# operacake.net
KiCad netlist of a schematic drawn in Altium Designer
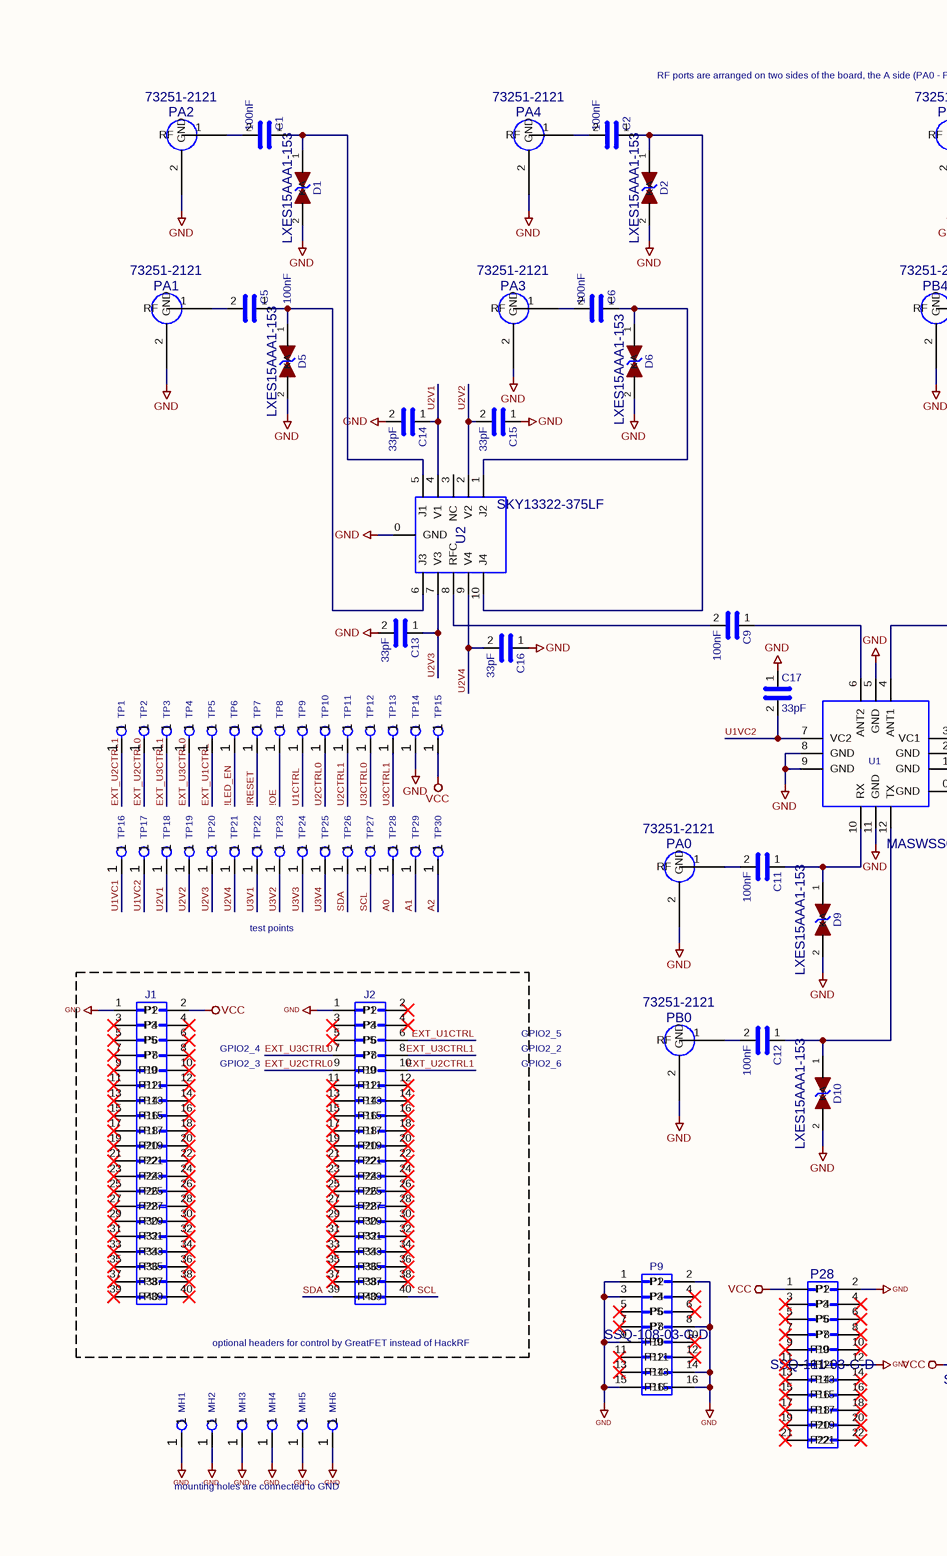
[diagram p0: operacake.SchDoc, left]
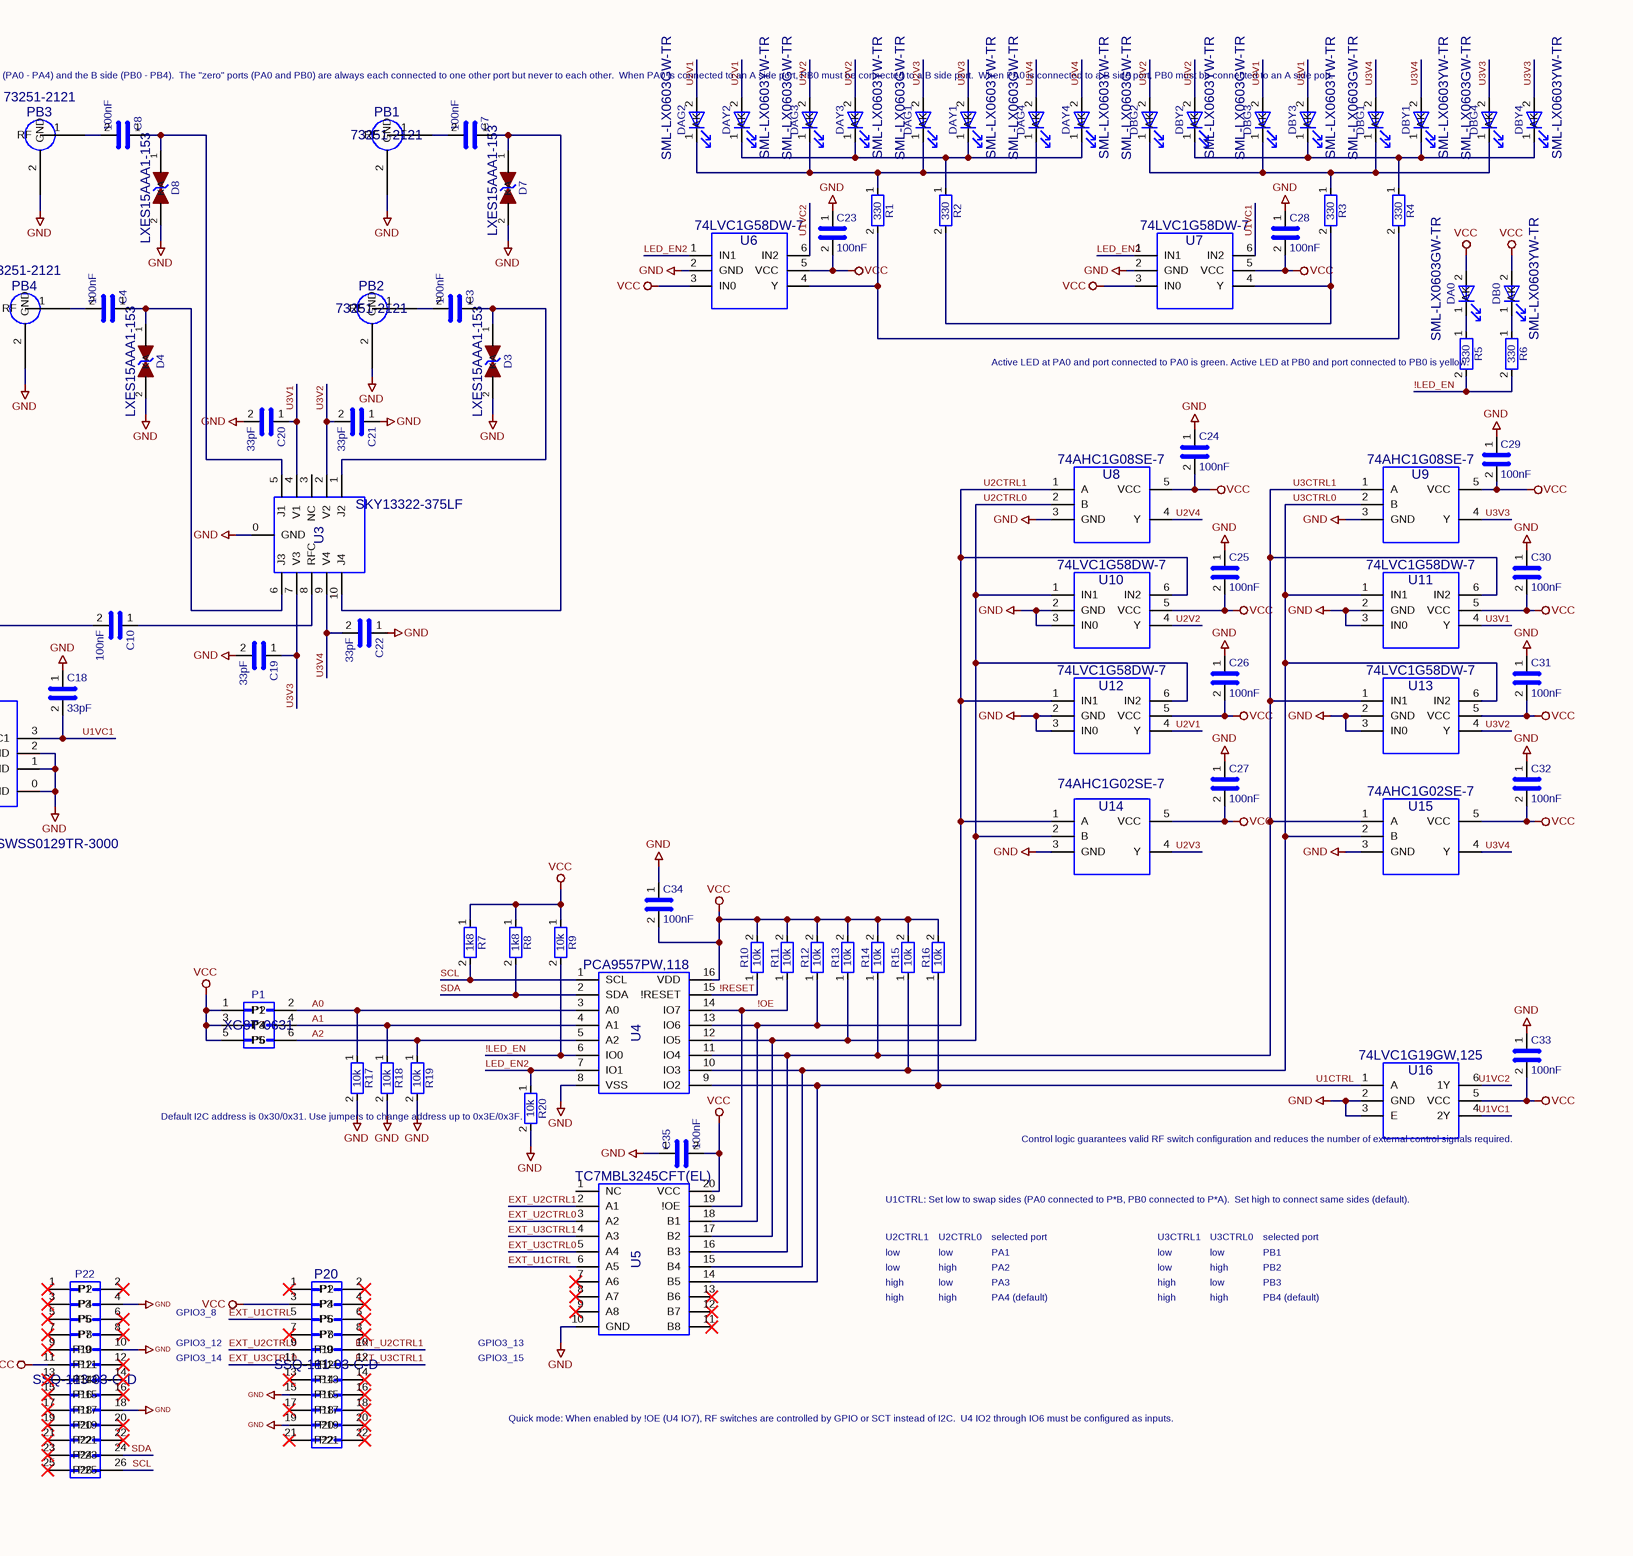
[diagram p1: operacake.SchDoc, right]

(export (version "E")
  (design (tool "Eeschema 10.0.6"))
  (components
    (comp (ref "C1")
      (value "100nF")
      (footprint "0402")
      (fields (field (name "MANUFACTURER") "Murata") (field (name "PART NUMBER") "GRM155R61A104KA01D"))
      (libsource (lib "operacake-rescue") (part "C"))
    )
    (comp (ref "C2")
      (value "100nF")
      (footprint "0402")
      (fields (field (name "MANUFACTURER") "Murata") (field (name "PART NUMBER") "GRM155R61A104KA01D"))
      (libsource (lib "operacake-rescue") (part "C"))
    )
    (comp (ref "C3")
      (value "100nF")
      (footprint "0402")
      (fields (field (name "MANUFACTURER") "Murata") (field (name "PART NUMBER") "GRM155R61A104KA01D"))
      (libsource (lib "operacake-rescue") (part "C"))
    )
    (comp (ref "C4")
      (value "100nF")
      (footprint "0402")
      (fields (field (name "MANUFACTURER") "Murata") (field (name "PART NUMBER") "GRM155R61A104KA01D"))
      (libsource (lib "operacake-rescue") (part "C"))
    )
    (comp (ref "C5")
      (value "100nF")
      (footprint "0402")
      (fields (field (name "MANUFACTURER") "Murata") (field (name "PART NUMBER") "GRM155R61A104KA01D"))
      (libsource (lib "operacake-rescue") (part "C"))
    )
    (comp (ref "C6")
      (value "100nF")
      (footprint "0402")
      (fields (field (name "MANUFACTURER") "Murata") (field (name "PART NUMBER") "GRM155R61A104KA01D"))
      (libsource (lib "operacake-rescue") (part "C"))
    )
    (comp (ref "C7")
      (value "100nF")
      (footprint "0402")
      (fields (field (name "MANUFACTURER") "Murata") (field (name "PART NUMBER") "GRM155R61A104KA01D"))
      (libsource (lib "operacake-rescue") (part "C"))
    )
    (comp (ref "C8")
      (value "100nF")
      (footprint "0402")
      (fields (field (name "MANUFACTURER") "Murata") (field (name "PART NUMBER") "GRM155R61A104KA01D"))
      (libsource (lib "operacake-rescue") (part "C"))
    )
    (comp (ref "C9")
      (value "100nF")
      (footprint "0402")
      (fields (field (name "MANUFACTURER") "Murata") (field (name "PART NUMBER") "GRM155R61A104KA01D"))
      (libsource (lib "operacake-rescue") (part "C"))
    )
    (comp (ref "C10")
      (value "100nF")
      (footprint "0402")
      (fields (field (name "MANUFACTURER") "Murata") (field (name "PART NUMBER") "GRM155R61A104KA01D"))
      (libsource (lib "operacake-rescue") (part "C"))
    )
    (comp (ref "C11")
      (value "100nF")
      (footprint "0402")
      (fields (field (name "MANUFACTURER") "Murata") (field (name "PART NUMBER") "GRM155R61A104KA01D"))
      (libsource (lib "operacake-rescue") (part "C"))
    )
    (comp (ref "C12")
      (value "100nF")
      (footprint "0402")
      (fields (field (name "MANUFACTURER") "Murata") (field (name "PART NUMBER") "GRM155R61A104KA01D"))
      (libsource (lib "operacake-rescue") (part "C"))
    )
    (comp (ref "C13")
      (value "33pF")
      (footprint "0402")
      (fields (field (name "MANUFACTURER") "Murata") (field (name "PART NUMBER") "GRM1555C1H330JA01D"))
      (libsource (lib "operacake-rescue") (part "C"))
    )
    (comp (ref "C14")
      (value "33pF")
      (footprint "0402")
      (fields (field (name "MANUFACTURER") "Murata") (field (name "PART NUMBER") "GRM1555C1H330JA01D"))
      (libsource (lib "operacake-rescue") (part "C"))
    )
    (comp (ref "C15")
      (value "33pF")
      (footprint "0402")
      (fields (field (name "MANUFACTURER") "Murata") (field (name "PART NUMBER") "GRM1555C1H330JA01D"))
      (libsource (lib "operacake-rescue") (part "C"))
    )
    (comp (ref "C16")
      (value "33pF")
      (footprint "0402")
      (fields (field (name "MANUFACTURER") "Murata") (field (name "PART NUMBER") "GRM1555C1H330JA01D"))
      (libsource (lib "operacake-rescue") (part "C"))
    )
    (comp (ref "C17")
      (value "33pF")
      (footprint "0402")
      (fields (field (name "MANUFACTURER") "Murata") (field (name "PART NUMBER") "GRM1555C1H330JA01D"))
      (libsource (lib "operacake-rescue") (part "C"))
    )
    (comp (ref "C18")
      (value "33pF")
      (footprint "0402")
      (fields (field (name "MANUFACTURER") "Murata") (field (name "PART NUMBER") "GRM1555C1H330JA01D"))
      (libsource (lib "operacake-rescue") (part "C"))
    )
    (comp (ref "C19")
      (value "33pF")
      (footprint "0402")
      (fields (field (name "MANUFACTURER") "Murata") (field (name "PART NUMBER") "GRM1555C1H330JA01D"))
      (libsource (lib "operacake-rescue") (part "C"))
    )
    (comp (ref "C20")
      (value "33pF")
      (footprint "0402")
      (fields (field (name "MANUFACTURER") "Murata") (field (name "PART NUMBER") "GRM1555C1H330JA01D"))
      (libsource (lib "operacake-rescue") (part "C"))
    )
    (comp (ref "C21")
      (value "33pF")
      (footprint "0402")
      (fields (field (name "MANUFACTURER") "Murata") (field (name "PART NUMBER") "GRM1555C1H330JA01D"))
      (libsource (lib "operacake-rescue") (part "C"))
    )
    (comp (ref "C22")
      (value "33pF")
      (footprint "0402")
      (fields (field (name "MANUFACTURER") "Murata") (field (name "PART NUMBER") "GRM1555C1H330JA01D"))
      (libsource (lib "operacake-rescue") (part "C"))
    )
    (comp (ref "C23")
      (value "100nF")
      (footprint "0402")
      (fields (field (name "MANUFACTURER") "Murata") (field (name "PART NUMBER") "GRM155R61A104KA01D"))
      (libsource (lib "operacake-rescue") (part "C"))
    )
    (comp (ref "C24")
      (value "100nF")
      (footprint "0402")
      (fields (field (name "MANUFACTURER") "Murata") (field (name "PART NUMBER") "GRM155R61A104KA01D"))
      (libsource (lib "operacake-rescue") (part "C"))
    )
    (comp (ref "C25")
      (value "100nF")
      (footprint "0402")
      (fields (field (name "MANUFACTURER") "Murata") (field (name "PART NUMBER") "GRM155R61A104KA01D"))
      (libsource (lib "operacake-rescue") (part "C"))
    )
    (comp (ref "C26")
      (value "100nF")
      (footprint "0402")
      (fields (field (name "MANUFACTURER") "Murata") (field (name "PART NUMBER") "GRM155R61A104KA01D"))
      (libsource (lib "operacake-rescue") (part "C"))
    )
    (comp (ref "C27")
      (value "100nF")
      (footprint "0402")
      (fields (field (name "MANUFACTURER") "Murata") (field (name "PART NUMBER") "GRM155R61A104KA01D"))
      (libsource (lib "operacake-rescue") (part "C"))
    )
    (comp (ref "C28")
      (value "100nF")
      (footprint "0402")
      (fields (field (name "MANUFACTURER") "Murata") (field (name "PART NUMBER") "GRM155R61A104KA01D"))
      (libsource (lib "operacake-rescue") (part "C"))
    )
    (comp (ref "C29")
      (value "100nF")
      (footprint "0402")
      (fields (field (name "MANUFACTURER") "Murata") (field (name "PART NUMBER") "GRM155R61A104KA01D"))
      (libsource (lib "operacake-rescue") (part "C"))
    )
    (comp (ref "C30")
      (value "100nF")
      (footprint "0402")
      (fields (field (name "MANUFACTURER") "Murata") (field (name "PART NUMBER") "GRM155R61A104KA01D"))
      (libsource (lib "operacake-rescue") (part "C"))
    )
    (comp (ref "C31")
      (value "100nF")
      (footprint "0402")
      (fields (field (name "MANUFACTURER") "Murata") (field (name "PART NUMBER") "GRM155R61A104KA01D"))
      (libsource (lib "operacake-rescue") (part "C"))
    )
    (comp (ref "C32")
      (value "100nF")
      (footprint "0402")
      (fields (field (name "MANUFACTURER") "Murata") (field (name "PART NUMBER") "GRM155R61A104KA01D"))
      (libsource (lib "operacake-rescue") (part "C"))
    )
    (comp (ref "C33")
      (value "100nF")
      (footprint "0402")
      (fields (field (name "MANUFACTURER") "Murata") (field (name "PART NUMBER") "GRM155R61A104KA01D"))
      (libsource (lib "operacake-rescue") (part "C"))
    )
    (comp (ref "C34")
      (value "100nF")
      (footprint "0402")
      (fields (field (name "MANUFACTURER") "Murata") (field (name "PART NUMBER") "GRM155R61A104KA01D"))
      (libsource (lib "operacake-rescue") (part "C"))
    )
    (comp (ref "C35")
      (value "100nF")
      (footprint "0402")
      (fields (field (name "MANUFACTURER") "Murata") (field (name "PART NUMBER") "GRM155R61A104KA01D"))
      (libsource (lib "operacake-rescue") (part "C"))
    )
    (comp (ref "D1")
      (value "GSG-DIODE-TVS-BI")
      (footprint "0402")
      (fields (field (name "MANUFACTURER") "Murata") (field (name "PART NUMBER") "LXES15AAA1-153"))
      (libsource (lib "hackrf") (part "GSG-DIODE-TVS-BI"))
    )
    (comp (ref "D2")
      (value "GSG-DIODE-TVS-BI")
      (footprint "0402")
      (fields (field (name "MANUFACTURER") "Murata") (field (name "PART NUMBER") "LXES15AAA1-153"))
      (libsource (lib "hackrf") (part "GSG-DIODE-TVS-BI"))
    )
    (comp (ref "D3")
      (value "GSG-DIODE-TVS-BI")
      (footprint "0402")
      (fields (field (name "MANUFACTURER") "Murata") (field (name "PART NUMBER") "LXES15AAA1-153"))
      (libsource (lib "hackrf") (part "GSG-DIODE-TVS-BI"))
    )
    (comp (ref "D4")
      (value "GSG-DIODE-TVS-BI")
      (footprint "0402")
      (fields (field (name "MANUFACTURER") "Murata") (field (name "PART NUMBER") "LXES15AAA1-153"))
      (libsource (lib "hackrf") (part "GSG-DIODE-TVS-BI"))
    )
    (comp (ref "D5")
      (value "GSG-DIODE-TVS-BI")
      (footprint "0402")
      (fields (field (name "MANUFACTURER") "Murata") (field (name "PART NUMBER") "LXES15AAA1-153"))
      (libsource (lib "hackrf") (part "GSG-DIODE-TVS-BI"))
    )
    (comp (ref "D6")
      (value "GSG-DIODE-TVS-BI")
      (footprint "0402")
      (fields (field (name "MANUFACTURER") "Murata") (field (name "PART NUMBER") "LXES15AAA1-153"))
      (libsource (lib "hackrf") (part "GSG-DIODE-TVS-BI"))
    )
    (comp (ref "D7")
      (value "GSG-DIODE-TVS-BI")
      (footprint "0402")
      (fields (field (name "MANUFACTURER") "Murata") (field (name "PART NUMBER") "LXES15AAA1-153"))
      (libsource (lib "hackrf") (part "GSG-DIODE-TVS-BI"))
    )
    (comp (ref "D8")
      (value "GSG-DIODE-TVS-BI")
      (footprint "0402")
      (fields (field (name "MANUFACTURER") "Murata") (field (name "PART NUMBER") "LXES15AAA1-153"))
      (libsource (lib "hackrf") (part "GSG-DIODE-TVS-BI"))
    )
    (comp (ref "D9")
      (value "GSG-DIODE-TVS-BI")
      (footprint "0402")
      (fields (field (name "MANUFACTURER") "Murata") (field (name "PART NUMBER") "LXES15AAA1-153"))
      (libsource (lib "hackrf") (part "GSG-DIODE-TVS-BI"))
    )
    (comp (ref "D10")
      (value "GSG-DIODE-TVS-BI")
      (footprint "0402")
      (fields (field (name "MANUFACTURER") "Murata") (field (name "PART NUMBER") "LXES15AAA1-153"))
      (libsource (lib "hackrf") (part "GSG-DIODE-TVS-BI"))
    )
    (comp (ref "DA0")
      (value "LED")
      (footprint "0603D")
      (fields (field (name "MANUFACTURER") "Lumex") (field (name "PART NUMBER") "SML-LX0603GW-TR"))
      (libsource (lib "operacake-rescue") (part "LED"))
    )
    (comp (ref "DAG1")
      (value "LED")
      (footprint "0603D")
      (fields (field (name "MANUFACTURER") "Lumex") (field (name "PART NUMBER") "SML-LX0603GW-TR"))
      (libsource (lib "operacake-rescue") (part "LED"))
    )
    (comp (ref "DAG2")
      (value "LED")
      (footprint "0603D")
      (fields (field (name "MANUFACTURER") "Lumex") (field (name "PART NUMBER") "SML-LX0603GW-TR"))
      (libsource (lib "operacake-rescue") (part "LED"))
    )
    (comp (ref "DAG3")
      (value "LED")
      (footprint "0603D")
      (fields (field (name "MANUFACTURER") "Lumex") (field (name "PART NUMBER") "SML-LX0603GW-TR"))
      (libsource (lib "operacake-rescue") (part "LED"))
    )
    (comp (ref "DAG4")
      (value "LED")
      (footprint "0603D")
      (fields (field (name "MANUFACTURER") "Lumex") (field (name "PART NUMBER") "SML-LX0603GW-TR"))
      (libsource (lib "operacake-rescue") (part "LED"))
    )
    (comp (ref "DAY1")
      (value "LED")
      (footprint "0603D")
      (fields (field (name "MANUFACTURER") "Lumex") (field (name "PART NUMBER") "SML-LX0603YW-TR"))
      (libsource (lib "operacake-rescue") (part "LED"))
    )
    (comp (ref "DAY2")
      (value "LED")
      (footprint "0603D")
      (fields (field (name "MANUFACTURER") "Lumex") (field (name "PART NUMBER") "SML-LX0603YW-TR"))
      (libsource (lib "operacake-rescue") (part "LED"))
    )
    (comp (ref "DAY3")
      (value "LED")
      (footprint "0603D")
      (fields (field (name "MANUFACTURER") "Lumex") (field (name "PART NUMBER") "SML-LX0603YW-TR"))
      (libsource (lib "operacake-rescue") (part "LED"))
    )
    (comp (ref "DAY4")
      (value "LED")
      (footprint "0603D")
      (fields (field (name "MANUFACTURER") "Lumex") (field (name "PART NUMBER") "SML-LX0603YW-TR"))
      (libsource (lib "operacake-rescue") (part "LED"))
    )
    (comp (ref "DB0")
      (value "LED")
      (footprint "0603D")
      (fields (field (name "MANUFACTURER") "Lumex") (field (name "PART NUMBER") "SML-LX0603YW-TR"))
      (libsource (lib "operacake-rescue") (part "LED"))
    )
    (comp (ref "DBG1")
      (value "LED")
      (footprint "0603D")
      (fields (field (name "MANUFACTURER") "Lumex") (field (name "PART NUMBER") "SML-LX0603GW-TR"))
      (libsource (lib "operacake-rescue") (part "LED"))
    )
    (comp (ref "DBG2")
      (value "LED")
      (footprint "0603D")
      (fields (field (name "MANUFACTURER") "Lumex") (field (name "PART NUMBER") "SML-LX0603GW-TR"))
      (libsource (lib "operacake-rescue") (part "LED"))
    )
    (comp (ref "DBG3")
      (value "LED")
      (footprint "0603D")
      (fields (field (name "MANUFACTURER") "Lumex") (field (name "PART NUMBER") "SML-LX0603GW-TR"))
      (libsource (lib "operacake-rescue") (part "LED"))
    )
    (comp (ref "DBG4")
      (value "LED")
      (footprint "0603D")
      (fields (field (name "MANUFACTURER") "Lumex") (field (name "PART NUMBER") "SML-LX0603GW-TR"))
      (libsource (lib "operacake-rescue") (part "LED"))
    )
    (comp (ref "DBY1")
      (value "LED")
      (footprint "0603D")
      (fields (field (name "MANUFACTURER") "Lumex") (field (name "PART NUMBER") "SML-LX0603YW-TR"))
      (libsource (lib "operacake-rescue") (part "LED"))
    )
    (comp (ref "DBY2")
      (value "LED")
      (footprint "0603D")
      (fields (field (name "MANUFACTURER") "Lumex") (field (name "PART NUMBER") "SML-LX0603YW-TR"))
      (libsource (lib "operacake-rescue") (part "LED"))
    )
    (comp (ref "DBY3")
      (value "LED")
      (footprint "0603D")
      (fields (field (name "MANUFACTURER") "Lumex") (field (name "PART NUMBER") "SML-LX0603YW-TR"))
      (libsource (lib "operacake-rescue") (part "LED"))
    )
    (comp (ref "DBY4")
      (value "LED")
      (footprint "0603D")
      (fields (field (name "MANUFACTURER") "Lumex") (field (name "PART NUMBER") "SML-LX0603YW-TR"))
      (libsource (lib "operacake-rescue") (part "LED"))
    )
    (comp (ref "J1")
      (value "CONN_02X20")
      (footprint "HEADER-2x20-REVERSE")
      (libsource (lib "operacake-rescue") (part "CONN_02X20"))
    )
    (comp (ref "J2")
      (value "CONN_02X20")
      (footprint "HEADER-2x20-REVERSE")
      (libsource (lib "operacake-rescue") (part "CONN_02X20"))
    )
    (comp (ref "MH1")
      (value "MOUNTING_HOLE")
      (footprint "HOLE126MIL-COPPER")
      (libsource (lib "operacake-rescue") (part "CONN_1"))
    )
    (comp (ref "MH2")
      (value "MOUNTING_HOLE")
      (footprint "HOLE126MIL-COPPER")
      (libsource (lib "operacake-rescue") (part "CONN_1"))
    )
    (comp (ref "MH3")
      (value "MOUNTING_HOLE")
      (footprint "HOLE126MIL-COPPER")
      (libsource (lib "operacake-rescue") (part "CONN_1"))
    )
    (comp (ref "MH4")
      (value "MOUNTING_HOLE")
      (footprint "HOLE126MIL-COPPER")
      (libsource (lib "operacake-rescue") (part "CONN_1"))
    )
    (comp (ref "MH5")
      (value "MOUNTING_HOLE")
      (footprint "HOLE126MIL-COPPER")
      (libsource (lib "operacake-rescue") (part "CONN_1"))
    )
    (comp (ref "MH6")
      (value "MOUNTING_HOLE")
      (footprint "HOLE126MIL-COPPER")
      (libsource (lib "operacake-rescue") (part "CONN_1"))
    )
    (comp (ref "P1")
      (value "ADDRESS")
      (footprint "HEADER-2x3")
      (fields (field (name "MANUFACTURER") "Omron") (field (name "PART NUMBER") "XG8T-0631"))
      (libsource (lib "operacake-rescue") (part "CONN_02X03"))
    )
    (comp (ref "P9")
      (value "BASEBAND")
      (footprint "HEADER-2x8")
      (fields (field (name "MANUFACTURER") "Samtec") (field (name "PART NUMBER") "SSQ-108-03-G-D"))
      (libsource (lib "operacake-rescue") (part "CONN_02X08"))
    )
    (comp (ref "P20")
      (value "GPIO")
      (footprint "HEADER-2x11")
      (fields (field (name "MANUFACTURER") "Samtec") (field (name "PART NUMBER") "SSQ-111-03-G-D"))
      (libsource (lib "operacake-rescue") (part "CONN_02X11"))
    )
    (comp (ref "P22")
      (value "I2S")
      (footprint "HEADER-2x13")
      (fields (field (name "MANUFACTURER") "Samtec") (field (name "PART NUMBER") "SSQ-113-03-G-D"))
      (libsource (lib "operacake-rescue") (part "CONN_02X13"))
    )
    (comp (ref "P28")
      (value "SD")
      (footprint "HEADER-2x11")
      (fields (field (name "MANUFACTURER") "Samtec") (field (name "PART NUMBER") "SSQ-111-03-G-D"))
      (libsource (lib "operacake-rescue") (part "CONN_02X11"))
    )
    (comp (ref "PA0")
      (value "GSG-RF-CONN")
      (footprint "GSG-SMA-73251-2120")
      (fields (field (name "MANUFACTURER") "Molex") (field (name "PART NUMBER") "73251-2121"))
      (libsource (lib "hackrf") (part "GSG-RF-CONN"))
    )
    (comp (ref "PA1")
      (value "GSG-RF-CONN")
      (footprint "GSG-SMA-73251-2120")
      (fields (field (name "MANUFACTURER") "Molex") (field (name "PART NUMBER") "73251-2121"))
      (libsource (lib "hackrf") (part "GSG-RF-CONN"))
    )
    (comp (ref "PA2")
      (value "GSG-RF-CONN")
      (footprint "GSG-SMA-73251-2120")
      (fields (field (name "MANUFACTURER") "Molex") (field (name "PART NUMBER") "73251-2121"))
      (libsource (lib "hackrf") (part "GSG-RF-CONN"))
    )
    (comp (ref "PA3")
      (value "GSG-RF-CONN")
      (footprint "GSG-SMA-73251-2120")
      (fields (field (name "MANUFACTURER") "Molex") (field (name "PART NUMBER") "73251-2121"))
      (libsource (lib "hackrf") (part "GSG-RF-CONN"))
    )
    (comp (ref "PA4")
      (value "GSG-RF-CONN")
      (footprint "GSG-SMA-73251-2120")
      (fields (field (name "MANUFACTURER") "Molex") (field (name "PART NUMBER") "73251-2121"))
      (libsource (lib "hackrf") (part "GSG-RF-CONN"))
    )
    (comp (ref "PB0")
      (value "GSG-RF-CONN")
      (footprint "GSG-SMA-73251-2120")
      (fields (field (name "MANUFACTURER") "Molex") (field (name "PART NUMBER") "73251-2121"))
      (libsource (lib "hackrf") (part "GSG-RF-CONN"))
    )
    (comp (ref "PB1")
      (value "GSG-RF-CONN")
      (footprint "GSG-SMA-73251-2120")
      (fields (field (name "MANUFACTURER") "Molex") (field (name "PART NUMBER") "73251-2121"))
      (libsource (lib "hackrf") (part "GSG-RF-CONN"))
    )
    (comp (ref "PB2")
      (value "GSG-RF-CONN")
      (footprint "GSG-SMA-73251-2120")
      (fields (field (name "MANUFACTURER") "Molex") (field (name "PART NUMBER") "73251-2121"))
      (libsource (lib "hackrf") (part "GSG-RF-CONN"))
    )
    (comp (ref "PB3")
      (value "GSG-RF-CONN")
      (footprint "GSG-SMA-73251-2120")
      (fields (field (name "MANUFACTURER") "Molex") (field (name "PART NUMBER") "73251-2121"))
      (libsource (lib "hackrf") (part "GSG-RF-CONN"))
    )
    (comp (ref "PB4")
      (value "GSG-RF-CONN")
      (footprint "GSG-SMA-73251-2120")
      (fields (field (name "MANUFACTURER") "Molex") (field (name "PART NUMBER") "73251-2121"))
      (libsource (lib "hackrf") (part "GSG-RF-CONN"))
    )
    (comp (ref "R1")
      (value "330")
      (footprint "0603")
      (fields (field (name "MANUFACTURER") "Stackpole") (field (name "PART NUMBER") "RMCF0603JT330R"))
      (libsource (lib "operacake-rescue") (part "R"))
    )
    (comp (ref "R2")
      (value "330")
      (footprint "0603")
      (fields (field (name "MANUFACTURER") "Stackpole") (field (name "PART NUMBER") "RMCF0603JT330R"))
      (libsource (lib "operacake-rescue") (part "R"))
    )
    (comp (ref "R3")
      (value "330")
      (footprint "0603")
      (fields (field (name "MANUFACTURER") "Stackpole") (field (name "PART NUMBER") "RMCF0603JT330R"))
      (libsource (lib "operacake-rescue") (part "R"))
    )
    (comp (ref "R4")
      (value "330")
      (footprint "0603")
      (fields (field (name "MANUFACTURER") "Stackpole") (field (name "PART NUMBER") "RMCF0603JT330R"))
      (libsource (lib "operacake-rescue") (part "R"))
    )
    (comp (ref "R5")
      (value "330")
      (footprint "0603")
      (fields (field (name "MANUFACTURER") "Stackpole") (field (name "PART NUMBER") "RMCF0603JT330R"))
      (libsource (lib "operacake-rescue") (part "R"))
    )
    (comp (ref "R6")
      (value "330")
      (footprint "0603")
      (fields (field (name "MANUFACTURER") "Stackpole") (field (name "PART NUMBER") "RMCF0603JT330R"))
      (libsource (lib "operacake-rescue") (part "R"))
    )
    (comp (ref "R7") (value "1k8") (footprint "0603") (libsource (lib "operacake-rescue") (part "R")))
    (comp (ref "R8") (value "1k8") (footprint "0603") (libsource (lib "operacake-rescue") (part "R")))
    (comp (ref "R9")
      (value "10k")
      (footprint "0603")
      (fields (field (name "MANUFACTURER") "Panasonic") (field (name "PART NUMBER") "ERJ-3GEYJ103V"))
      (libsource (lib "operacake-rescue") (part "R"))
    )
    (comp (ref "R10")
      (value "10k")
      (footprint "0603")
      (fields (field (name "MANUFACTURER") "Panasonic") (field (name "PART NUMBER") "ERJ-3GEYJ103V"))
      (libsource (lib "") (part "R_1"))
    )
    (comp (ref "R11")
      (value "10k")
      (footprint "0603")
      (fields (field (name "MANUFACTURER") "Panasonic") (field (name "PART NUMBER") "ERJ-3GEYJ103V"))
      (libsource (lib "") (part "R_1"))
    )
    (comp (ref "R12")
      (value "10k")
      (footprint "0603")
      (fields (field (name "MANUFACTURER") "Panasonic") (field (name "PART NUMBER") "ERJ-3GEYJ103V"))
      (libsource (lib "") (part "R_1"))
    )
    (comp (ref "R13")
      (value "10k")
      (footprint "0603")
      (fields (field (name "MANUFACTURER") "Panasonic") (field (name "PART NUMBER") "ERJ-3GEYJ103V"))
      (libsource (lib "") (part "R_1"))
    )
    (comp (ref "R14")
      (value "10k")
      (footprint "0603")
      (fields (field (name "MANUFACTURER") "Panasonic") (field (name "PART NUMBER") "ERJ-3GEYJ103V"))
      (libsource (lib "") (part "R_1"))
    )
    (comp (ref "R15")
      (value "10k")
      (footprint "0603")
      (fields (field (name "MANUFACTURER") "Panasonic") (field (name "PART NUMBER") "ERJ-3GEYJ103V"))
      (libsource (lib "") (part "R_1"))
    )
    (comp (ref "R16")
      (value "10k")
      (footprint "0603")
      (fields (field (name "MANUFACTURER") "Panasonic") (field (name "PART NUMBER") "ERJ-3GEYJ103V"))
      (libsource (lib "") (part "R_1"))
    )
    (comp (ref "R17")
      (value "10k")
      (footprint "0603")
      (fields (field (name "MANUFACTURER") "Panasonic") (field (name "PART NUMBER") "ERJ-3GEYJ103V"))
      (libsource (lib "operacake-rescue") (part "R"))
    )
    (comp (ref "R18")
      (value "10k")
      (footprint "0603")
      (fields (field (name "MANUFACTURER") "Panasonic") (field (name "PART NUMBER") "ERJ-3GEYJ103V"))
      (libsource (lib "operacake-rescue") (part "R"))
    )
    (comp (ref "R19")
      (value "10k")
      (footprint "0603")
      (fields (field (name "MANUFACTURER") "Panasonic") (field (name "PART NUMBER") "ERJ-3GEYJ103V"))
      (libsource (lib "operacake-rescue") (part "R"))
    )
    (comp (ref "R20")
      (value "10k")
      (footprint "0603")
      (fields (field (name "MANUFACTURER") "Panasonic") (field (name "PART NUMBER") "ERJ-3GEYJ103V"))
      (libsource (lib "operacake-rescue") (part "R"))
    )
    (comp (ref "TP1")
      (value "CONN_1")
      (footprint "TESTPOINT-50MIL")
      (libsource (lib "operacake-rescue") (part "CONN_1"))
    )
    (comp (ref "TP2")
      (value "CONN_1")
      (footprint "TESTPOINT-50MIL")
      (libsource (lib "operacake-rescue") (part "CONN_1"))
    )
    (comp (ref "TP3")
      (value "CONN_1")
      (footprint "TESTPOINT-50MIL")
      (libsource (lib "operacake-rescue") (part "CONN_1"))
    )
    (comp (ref "TP4")
      (value "CONN_1")
      (footprint "TESTPOINT-50MIL")
      (libsource (lib "operacake-rescue") (part "CONN_1"))
    )
    (comp (ref "TP5")
      (value "CONN_1")
      (footprint "TESTPOINT-50MIL")
      (libsource (lib "operacake-rescue") (part "CONN_1"))
    )
    (comp (ref "TP6")
      (value "CONN_1")
      (footprint "TESTPOINT-50MIL")
      (libsource (lib "operacake-rescue") (part "CONN_1"))
    )
    (comp (ref "TP7")
      (value "CONN_1")
      (footprint "TESTPOINT-50MIL")
      (libsource (lib "operacake-rescue") (part "CONN_1"))
    )
    (comp (ref "TP8")
      (value "CONN_1")
      (footprint "TESTPOINT-50MIL")
      (libsource (lib "operacake-rescue") (part "CONN_1"))
    )
    (comp (ref "TP9")
      (value "CONN_1")
      (footprint "TESTPOINT-50MIL")
      (libsource (lib "operacake-rescue") (part "CONN_1"))
    )
    (comp (ref "TP10")
      (value "CONN_1")
      (footprint "TESTPOINT-50MIL")
      (libsource (lib "operacake-rescue") (part "CONN_1"))
    )
    (comp (ref "TP11")
      (value "CONN_1")
      (footprint "TESTPOINT-50MIL")
      (libsource (lib "operacake-rescue") (part "CONN_1"))
    )
    (comp (ref "TP12")
      (value "CONN_1")
      (footprint "TESTPOINT-50MIL")
      (libsource (lib "operacake-rescue") (part "CONN_1"))
    )
    (comp (ref "TP13")
      (value "CONN_1")
      (footprint "TESTPOINT-50MIL")
      (libsource (lib "operacake-rescue") (part "CONN_1"))
    )
    (comp (ref "TP14")
      (value "CONN_1")
      (footprint "TESTPOINT-50MIL")
      (libsource (lib "operacake-rescue") (part "CONN_1"))
    )
    (comp (ref "TP15")
      (value "CONN_1")
      (footprint "TESTPOINT-50MIL")
      (libsource (lib "operacake-rescue") (part "CONN_1"))
    )
    (comp (ref "TP16")
      (value "CONN_1")
      (footprint "TESTPOINT-50MIL")
      (libsource (lib "operacake-rescue") (part "CONN_1"))
    )
    (comp (ref "TP17")
      (value "CONN_1")
      (footprint "TESTPOINT-50MIL")
      (libsource (lib "operacake-rescue") (part "CONN_1"))
    )
    (comp (ref "TP18")
      (value "CONN_1")
      (footprint "TESTPOINT-50MIL")
      (libsource (lib "operacake-rescue") (part "CONN_1"))
    )
    (comp (ref "TP19")
      (value "CONN_1")
      (footprint "TESTPOINT-50MIL")
      (libsource (lib "operacake-rescue") (part "CONN_1"))
    )
    (comp (ref "TP20")
      (value "CONN_1")
      (footprint "TESTPOINT-50MIL")
      (libsource (lib "operacake-rescue") (part "CONN_1"))
    )
    (comp (ref "TP21")
      (value "CONN_1")
      (footprint "TESTPOINT-50MIL")
      (libsource (lib "operacake-rescue") (part "CONN_1"))
    )
    (comp (ref "TP22")
      (value "CONN_1")
      (footprint "TESTPOINT-50MIL")
      (libsource (lib "operacake-rescue") (part "CONN_1"))
    )
    (comp (ref "TP23")
      (value "CONN_1")
      (footprint "TESTPOINT-50MIL")
      (libsource (lib "operacake-rescue") (part "CONN_1"))
    )
    (comp (ref "TP24")
      (value "CONN_1")
      (footprint "TESTPOINT-50MIL")
      (libsource (lib "operacake-rescue") (part "CONN_1"))
    )
    (comp (ref "TP25")
      (value "CONN_1")
      (footprint "TESTPOINT-50MIL")
      (libsource (lib "operacake-rescue") (part "CONN_1"))
    )
    (comp (ref "TP26")
      (value "CONN_1")
      (footprint "TESTPOINT-50MIL")
      (libsource (lib "operacake-rescue") (part "CONN_1"))
    )
    (comp (ref "TP27")
      (value "CONN_1")
      (footprint "TESTPOINT-50MIL")
      (libsource (lib "operacake-rescue") (part "CONN_1"))
    )
    (comp (ref "TP28")
      (value "CONN_1")
      (footprint "TESTPOINT-50MIL")
      (libsource (lib "operacake-rescue") (part "CONN_1"))
    )
    (comp (ref "TP29")
      (value "CONN_1")
      (footprint "TESTPOINT-50MIL")
      (libsource (lib "operacake-rescue") (part "CONN_1"))
    )
    (comp (ref "TP30")
      (value "CONN_1")
      (footprint "TESTPOINT-50MIL")
      (libsource (lib "operacake-rescue") (part "CONN_1"))
    )
    (comp (ref "U1")
      (value "MASWSS0129")
      (footprint "QFN12-3")
      (fields (field (name "MANUFACTURER") "M/A-Com") (field (name "PART NUMBER") "MASWSS0129TR-3000"))
      (libsource (lib "gsg-symbols") (part "MASWSS0129"))
    )
    (comp (ref "U2")
      (value "SKY13322")
      (footprint "SKY13322-375LF")
      (fields (field (name "MANUFACTURER") "Skyworks") (field (name "PART NUMBER") "SKY13322-375LF"))
      (libsource (lib "gsg-symbols") (part "SKY13322"))
    )
    (comp (ref "U3")
      (value "SKY13322")
      (footprint "SKY13322-375LF")
      (fields (field (name "MANUFACTURER") "Skyworks") (field (name "PART NUMBER") "SKY13322-375LF"))
      (libsource (lib "gsg-symbols") (part "SKY13322"))
    )
    (comp (ref "U4")
      (value "PCA9557")
      (footprint "TSSOP16")
      (fields (field (name "MANUFACTURER") "NXP") (field (name "PART NUMBER") "PCA9557PW,118"))
      (libsource (lib "gsg-symbols") (part "PCA9557"))
    )
    (comp (ref "U5")
      (value "TC7MBL3245CFT")
      (footprint "TSSOP20")
      (fields (field (name "MANUFACTURER") "Toshiba") (field (name "PART NUMBER") "TC7MBL3245CFT(EL)"))
      (libsource (lib "gsg-symbols") (part "TC7MBL3245CFT"))
    )
    (comp (ref "U6")
      (value "74LVC1G58")
      (footprint "SOT363")
      (fields (field (name "MANUFACTURER") "Diodes Inc.") (field (name "PART NUMBER") "74LVC1G58DW-7"))
      (libsource (lib "gsg-symbols") (part "74LVC1G58"))
    )
    (comp (ref "U7")
      (value "74LVC1G58")
      (footprint "SOT363")
      (fields (field (name "MANUFACTURER") "Diodes Inc.") (field (name "PART NUMBER") "74LVC1G58DW-7"))
      (libsource (lib "gsg-symbols") (part "74LVC1G58"))
    )
    (comp (ref "U8")
      (value "74AHC1G08")
      (footprint "SOT353-1")
      (fields (field (name "MANUFACTURER") "Diodes Inc.") (field (name "PART NUMBER") "74AHC1G08SE-7"))
      (libsource (lib "gsg-symbols") (part "74AHC1G08"))
    )
    (comp (ref "U9")
      (value "74AHC1G08")
      (footprint "SOT353-1")
      (fields (field (name "MANUFACTURER") "Diodes Inc.") (field (name "PART NUMBER") "74AHC1G08SE-7"))
      (libsource (lib "gsg-symbols") (part "74AHC1G08"))
    )
    (comp (ref "U10")
      (value "74LVC1G58")
      (footprint "SOT363")
      (fields (field (name "MANUFACTURER") "Diodes Inc.") (field (name "PART NUMBER") "74LVC1G58DW-7"))
      (libsource (lib "gsg-symbols") (part "74LVC1G58"))
    )
    (comp (ref "U11")
      (value "74LVC1G58")
      (footprint "SOT363")
      (fields (field (name "MANUFACTURER") "Diodes Inc.") (field (name "PART NUMBER") "74LVC1G58DW-7"))
      (libsource (lib "gsg-symbols") (part "74LVC1G58"))
    )
    (comp (ref "U12")
      (value "74LVC1G58")
      (footprint "SOT363")
      (fields (field (name "MANUFACTURER") "Diodes Inc.") (field (name "PART NUMBER") "74LVC1G58DW-7"))
      (libsource (lib "gsg-symbols") (part "74LVC1G58"))
    )
    (comp (ref "U13")
      (value "74LVC1G58")
      (footprint "SOT363")
      (fields (field (name "MANUFACTURER") "Diodes Inc.") (field (name "PART NUMBER") "74LVC1G58DW-7"))
      (libsource (lib "gsg-symbols") (part "74LVC1G58"))
    )
    (comp (ref "U14")
      (value "74AHC1G02")
      (footprint "SOT353-1")
      (fields (field (name "MANUFACTURER") "Diodes Inc.") (field (name "PART NUMBER") "74AHC1G02SE-7"))
      (libsource (lib "gsg-symbols") (part "74AHC1G08"))
    )
    (comp (ref "U15")
      (value "74AHC1G02")
      (footprint "SOT353-1")
      (fields (field (name "MANUFACTURER") "Diodes Inc.") (field (name "PART NUMBER") "74AHC1G02SE-7"))
      (libsource (lib "gsg-symbols") (part "74AHC1G08"))
    )
    (comp (ref "U16")
      (value "74LVC1G19")
      (footprint "SOT363")
      (fields (field (name "MANUFACTURER") "NXP") (field (name "PART NUMBER") "74LVC1G19GW,125"))
      (libsource (lib "gsg-symbols") (part "74LVC1G19"))
    )
  )
  (nets
    (net (code "1") (name "/!LED_EN") (class "Default")
      (node (ref "R5") (pin "2") (pinfunction "2_2") (pintype "passive"))
      (node (ref "R6") (pin "2") (pinfunction "2_2") (pintype "passive"))
      (node (ref "R9") (pin "2") (pinfunction "2_2") (pintype "passive"))
      (node (ref "TP6") (pin "1") (pinfunction "1_1") (pintype "passive"))
      (node (ref "U4") (pin "6") (pinfunction "IO0_6") (pintype "passive"))
    )
    (net (code "2") (name "/!OE") (class "Default")
      (node (ref "R11") (pin "1") (pinfunction "1_1") (pintype "passive"))
      (node (ref "TP8") (pin "1") (pinfunction "1_1") (pintype "passive"))
      (node (ref "U4") (pin "14") (pinfunction "IO7_14") (pintype "passive"))
      (node (ref "U5") (pin "19") (pinfunction "!OE_19") (pintype "passive"))
    )
    (net (code "3") (name "/!RESET") (class "Default")
      (node (ref "R10") (pin "1") (pinfunction "1_1") (pintype "passive"))
      (node (ref "TP7") (pin "1") (pinfunction "1_1") (pintype "passive"))
      (node (ref "U4") (pin "15") (pinfunction "!RESET_15") (pintype "passive"))
    )
    (net (code "4") (name "/A0") (class "Default")
      (node (ref "P1") (pin "2") (pinfunction "P2_2") (pintype "passive"))
      (node (ref "R17") (pin "1") (pinfunction "1_1") (pintype "passive"))
      (node (ref "TP28") (pin "1") (pinfunction "1_1") (pintype "passive"))
      (node (ref "U4") (pin "3") (pinfunction "A0_3") (pintype "passive"))
    )
    (net (code "5") (name "/A1") (class "Default")
      (node (ref "P1") (pin "4") (pinfunction "P4_4") (pintype "passive"))
      (node (ref "R18") (pin "1") (pinfunction "1_1") (pintype "passive"))
      (node (ref "TP29") (pin "1") (pinfunction "1_1") (pintype "passive"))
      (node (ref "U4") (pin "4") (pinfunction "A1_4") (pintype "passive"))
    )
    (net (code "6") (name "/A2") (class "Default")
      (node (ref "P1") (pin "6") (pinfunction "P6_6") (pintype "passive"))
      (node (ref "R19") (pin "1") (pinfunction "1_1") (pintype "passive"))
      (node (ref "TP30") (pin "1") (pinfunction "1_1") (pintype "passive"))
      (node (ref "U4") (pin "5") (pinfunction "A2_5") (pintype "passive"))
    )
    (net (code "7") (name "/EXT_U1CTRL") (class "Default")
      (node (ref "J2") (pin "6") (pinfunction "P6_6") (pintype "passive"))
      (node (ref "P20") (pin "5") (pinfunction "P5_5") (pintype "passive"))
      (node (ref "TP5") (pin "1") (pinfunction "1_1") (pintype "passive"))
      (node (ref "U5") (pin "6") (pinfunction "A5_6") (pintype "passive"))
    )
    (net (code "8") (name "/EXT_U2CTRL0") (class "Default")
      (node (ref "J2") (pin "9") (pinfunction "P9_9") (pintype "passive"))
      (node (ref "P20") (pin "9") (pinfunction "P9_9") (pintype "passive"))
      (node (ref "TP2") (pin "1") (pinfunction "1_1") (pintype "passive"))
      (node (ref "U5") (pin "3") (pinfunction "A2_3") (pintype "passive"))
    )
    (net (code "9") (name "/EXT_U2CTRL1") (class "Default")
      (node (ref "J2") (pin "10") (pinfunction "P10_10") (pintype "passive"))
      (node (ref "P20") (pin "10") (pinfunction "P10_10") (pintype "passive"))
      (node (ref "TP1") (pin "1") (pinfunction "1_1") (pintype "passive"))
      (node (ref "U5") (pin "2") (pinfunction "A1_2") (pintype "passive"))
    )
    (net (code "10") (name "/EXT_U3CTRL0") (class "Default")
      (node (ref "J2") (pin "7") (pinfunction "P7_7") (pintype "passive"))
      (node (ref "P20") (pin "11") (pinfunction "P11_11") (pintype "passive"))
      (node (ref "TP4") (pin "1") (pinfunction "1_1") (pintype "passive"))
      (node (ref "U5") (pin "5") (pinfunction "A4_5") (pintype "passive"))
    )
    (net (code "11") (name "/EXT_U3CTRL1") (class "Default")
      (node (ref "J2") (pin "8") (pinfunction "P8_8") (pintype "passive"))
      (node (ref "P20") (pin "12") (pinfunction "P12_12") (pintype "passive"))
      (node (ref "TP3") (pin "1") (pinfunction "1_1") (pintype "passive"))
      (node (ref "U5") (pin "4") (pinfunction "A3_4") (pintype "passive"))
    )
    (net (code "12") (name "/LED_EN2") (class "Default")
      (node (ref "R20") (pin "1") (pinfunction "1_1") (pintype "passive"))
      (node (ref "U4") (pin "7") (pinfunction "IO1_7") (pintype "passive"))
      (node (ref "U6") (pin "1") (pinfunction "IN1_1") (pintype "passive"))
      (node (ref "U7") (pin "1") (pinfunction "IN1_1") (pintype "passive"))
    )
    (net (code "13") (name "/SCL") (class "Default")
      (node (ref "J2") (pin "40") (pinfunction "P40_40") (pintype "passive"))
      (node (ref "P22") (pin "26") (pinfunction "P26_26") (pintype "passive"))
      (node (ref "R7") (pin "2") (pinfunction "2_2") (pintype "passive"))
      (node (ref "TP27") (pin "1") (pinfunction "1_1") (pintype "passive"))
      (node (ref "U4") (pin "1") (pinfunction "SCL_1") (pintype "passive"))
    )
    (net (code "14") (name "/SDA") (class "Default")
      (node (ref "J2") (pin "39") (pinfunction "P39_39") (pintype "passive"))
      (node (ref "P22") (pin "24") (pinfunction "P24_24") (pintype "passive"))
      (node (ref "R8") (pin "2") (pinfunction "2_2") (pintype "passive"))
      (node (ref "TP26") (pin "1") (pinfunction "1_1") (pintype "passive"))
      (node (ref "U4") (pin "2") (pinfunction "SDA_2") (pintype "passive"))
    )
    (net (code "15") (name "/U1CTRL") (class "Default")
      (node (ref "R16") (pin "1") (pinfunction "1_1") (pintype "passive"))
      (node (ref "TP9") (pin "1") (pinfunction "1_1") (pintype "passive"))
      (node (ref "U16") (pin "1") (pinfunction "A_1") (pintype "passive"))
      (node (ref "U4") (pin "9") (pinfunction "IO2_9") (pintype "passive"))
      (node (ref "U5") (pin "14") (pinfunction "B5_14") (pintype "passive"))
    )
    (net (code "16") (name "/U1VC1") (class "Default")
      (node (ref "C18") (pin "2") (pinfunction "2_2") (pintype "passive"))
      (node (ref "TP16") (pin "1") (pinfunction "1_1") (pintype "passive"))
      (node (ref "U1") (pin "3") (pinfunction "VC1_3") (pintype "passive"))
      (node (ref "U16") (pin "4") (pinfunction "2Y_4") (pintype "passive"))
      (node (ref "U7") (pin "6") (pinfunction "IN2_6") (pintype "passive"))
    )
    (net (code "17") (name "/U1VC2") (class "Default")
      (node (ref "C17") (pin "2") (pinfunction "2_2") (pintype "passive"))
      (node (ref "TP17") (pin "1") (pinfunction "1_1") (pintype "passive"))
      (node (ref "U1") (pin "7") (pinfunction "VC2_7") (pintype "passive"))
      (node (ref "U16") (pin "6") (pinfunction "1Y_6") (pintype "passive"))
      (node (ref "U6") (pin "6") (pinfunction "IN2_6") (pintype "passive"))
    )
    (net (code "18") (name "/U2CTRL0") (class "Default")
      (node (ref "R13") (pin "1") (pinfunction "1_1") (pintype "passive"))
      (node (ref "TP10") (pin "1") (pinfunction "1_1") (pintype "passive"))
      (node (ref "U10") (pin "1") (pinfunction "IN1_1") (pintype "passive"))
      (node (ref "U12") (pin "6") (pinfunction "IN2_6") (pintype "passive"))
      (node (ref "U14") (pin "2") (pinfunction "B_2") (pintype "passive"))
      (node (ref "U4") (pin "12") (pinfunction "IO5_12") (pintype "passive"))
      (node (ref "U5") (pin "17") (pinfunction "B2_17") (pintype "passive"))
      (node (ref "U8") (pin "2") (pinfunction "B_2") (pintype "passive"))
    )
    (net (code "19") (name "/U2CTRL1") (class "Default")
      (node (ref "R12") (pin "1") (pinfunction "1_1") (pintype "passive"))
      (node (ref "TP11") (pin "1") (pinfunction "1_1") (pintype "passive"))
      (node (ref "U10") (pin "6") (pinfunction "IN2_6") (pintype "passive"))
      (node (ref "U12") (pin "1") (pinfunction "IN1_1") (pintype "passive"))
      (node (ref "U14") (pin "1") (pinfunction "A_1") (pintype "passive"))
      (node (ref "U4") (pin "13") (pinfunction "IO6_13") (pintype "passive"))
      (node (ref "U5") (pin "18") (pinfunction "B1_18") (pintype "passive"))
      (node (ref "U8") (pin "1") (pinfunction "A_1") (pintype "passive"))
    )
    (net (code "20") (name "/U2V1") (class "Default")
      (node (ref "C14") (pin "1") (pinfunction "1_1") (pintype "passive"))
      (node (ref "DAG2") (pin "2") (pinfunction "A_2") (pintype "passive"))
      (node (ref "DAY2") (pin "2") (pinfunction "A_2") (pintype "passive"))
      (node (ref "TP18") (pin "1") (pinfunction "1_1") (pintype "passive"))
      (node (ref "U12") (pin "4") (pinfunction "Y_4") (pintype "passive"))
      (node (ref "U2") (pin "4") (pinfunction "V1_4") (pintype "passive"))
    )
    (net (code "21") (name "/U2V2") (class "Default")
      (node (ref "C15") (pin "2") (pinfunction "2_2") (pintype "passive"))
      (node (ref "DAG3") (pin "2") (pinfunction "A_2") (pintype "passive"))
      (node (ref "DAY3") (pin "2") (pinfunction "A_2") (pintype "passive"))
      (node (ref "TP19") (pin "1") (pinfunction "1_1") (pintype "passive"))
      (node (ref "U10") (pin "4") (pinfunction "Y_4") (pintype "passive"))
      (node (ref "U2") (pin "2") (pinfunction "V2_2") (pintype "passive"))
    )
    (net (code "22") (name "/U2V3") (class "Default")
      (node (ref "C13") (pin "1") (pinfunction "1_1") (pintype "passive"))
      (node (ref "DAG1") (pin "2") (pinfunction "A_2") (pintype "passive"))
      (node (ref "DAY1") (pin "2") (pinfunction "A_2") (pintype "passive"))
      (node (ref "TP20") (pin "1") (pinfunction "1_1") (pintype "passive"))
      (node (ref "U14") (pin "4") (pinfunction "Y_4") (pintype "passive"))
      (node (ref "U2") (pin "7") (pinfunction "V3_7") (pintype "passive"))
    )
    (net (code "23") (name "/U2V4") (class "Default")
      (node (ref "C16") (pin "2") (pinfunction "2_2") (pintype "passive"))
      (node (ref "DAG4") (pin "2") (pinfunction "A_2") (pintype "passive"))
      (node (ref "DAY4") (pin "2") (pinfunction "A_2") (pintype "passive"))
      (node (ref "TP21") (pin "1") (pinfunction "1_1") (pintype "passive"))
      (node (ref "U2") (pin "9") (pinfunction "V4_9") (pintype "passive"))
      (node (ref "U8") (pin "4") (pinfunction "Y_4") (pintype "passive"))
    )
    (net (code "24") (name "/U3CTRL0") (class "Default")
      (node (ref "R15") (pin "1") (pinfunction "1_1") (pintype "passive"))
      (node (ref "TP12") (pin "1") (pinfunction "1_1") (pintype "passive"))
      (node (ref "U11") (pin "1") (pinfunction "IN1_1") (pintype "passive"))
      (node (ref "U13") (pin "6") (pinfunction "IN2_6") (pintype "passive"))
      (node (ref "U15") (pin "2") (pinfunction "B_2") (pintype "passive"))
      (node (ref "U4") (pin "10") (pinfunction "IO3_10") (pintype "passive"))
      (node (ref "U5") (pin "15") (pinfunction "B4_15") (pintype "passive"))
      (node (ref "U9") (pin "2") (pinfunction "B_2") (pintype "passive"))
    )
    (net (code "25") (name "/U3CTRL1") (class "Default")
      (node (ref "R14") (pin "1") (pinfunction "1_1") (pintype "passive"))
      (node (ref "TP13") (pin "1") (pinfunction "1_1") (pintype "passive"))
      (node (ref "U11") (pin "6") (pinfunction "IN2_6") (pintype "passive"))
      (node (ref "U13") (pin "1") (pinfunction "IN1_1") (pintype "passive"))
      (node (ref "U15") (pin "1") (pinfunction "A_1") (pintype "passive"))
      (node (ref "U4") (pin "11") (pinfunction "IO4_11") (pintype "passive"))
      (node (ref "U5") (pin "16") (pinfunction "B3_16") (pintype "passive"))
      (node (ref "U9") (pin "1") (pinfunction "A_1") (pintype "passive"))
    )
    (net (code "26") (name "/U3V1") (class "Default")
      (node (ref "C20") (pin "1") (pinfunction "1_1") (pintype "passive"))
      (node (ref "DBG3") (pin "2") (pinfunction "A_2") (pintype "passive"))
      (node (ref "DBY3") (pin "2") (pinfunction "A_2") (pintype "passive"))
      (node (ref "TP22") (pin "1") (pinfunction "1_1") (pintype "passive"))
      (node (ref "U11") (pin "4") (pinfunction "Y_4") (pintype "passive"))
      (node (ref "U3") (pin "4") (pinfunction "V1_4") (pintype "passive"))
    )
    (net (code "27") (name "/U3V2") (class "Default")
      (node (ref "C21") (pin "2") (pinfunction "2_2") (pintype "passive"))
      (node (ref "DBG2") (pin "2") (pinfunction "A_2") (pintype "passive"))
      (node (ref "DBY2") (pin "2") (pinfunction "A_2") (pintype "passive"))
      (node (ref "TP23") (pin "1") (pinfunction "1_1") (pintype "passive"))
      (node (ref "U13") (pin "4") (pinfunction "Y_4") (pintype "passive"))
      (node (ref "U3") (pin "2") (pinfunction "V2_2") (pintype "passive"))
    )
    (net (code "28") (name "/U3V3") (class "Default")
      (node (ref "C19") (pin "1") (pinfunction "1_1") (pintype "passive"))
      (node (ref "DBG4") (pin "2") (pinfunction "A_2") (pintype "passive"))
      (node (ref "DBY4") (pin "2") (pinfunction "A_2") (pintype "passive"))
      (node (ref "TP24") (pin "1") (pinfunction "1_1") (pintype "passive"))
      (node (ref "U3") (pin "7") (pinfunction "V3_7") (pintype "passive"))
      (node (ref "U9") (pin "4") (pinfunction "Y_4") (pintype "passive"))
    )
    (net (code "29") (name "/U3V4") (class "Default")
      (node (ref "C22") (pin "2") (pinfunction "2_2") (pintype "passive"))
      (node (ref "DBG1") (pin "2") (pinfunction "A_2") (pintype "passive"))
      (node (ref "DBY1") (pin "2") (pinfunction "A_2") (pintype "passive"))
      (node (ref "TP25") (pin "1") (pinfunction "1_1") (pintype "passive"))
      (node (ref "U15") (pin "4") (pinfunction "Y_4") (pintype "passive"))
      (node (ref "U3") (pin "9") (pinfunction "V4_9") (pintype "passive"))
    )
    (net (code "30") (name "GND") (class "Default")
      (node (ref "C13") (pin "2") (pinfunction "2_2") (pintype "passive"))
      (node (ref "C14") (pin "2") (pinfunction "2_2") (pintype "passive"))
      (node (ref "C15") (pin "1") (pinfunction "1_1") (pintype "passive"))
      (node (ref "C16") (pin "1") (pinfunction "1_1") (pintype "passive"))
      (node (ref "C17") (pin "1") (pinfunction "1_1") (pintype "passive"))
      (node (ref "C18") (pin "1") (pinfunction "1_1") (pintype "passive"))
      (node (ref "C19") (pin "2") (pinfunction "2_2") (pintype "passive"))
      (node (ref "C20") (pin "2") (pinfunction "2_2") (pintype "passive"))
      (node (ref "C21") (pin "1") (pinfunction "1_1") (pintype "passive"))
      (node (ref "C22") (pin "1") (pinfunction "1_1") (pintype "passive"))
      (node (ref "C23") (pin "1") (pinfunction "1_1") (pintype "passive"))
      (node (ref "C24") (pin "1") (pinfunction "1_1") (pintype "passive"))
      (node (ref "C25") (pin "1") (pinfunction "1_1") (pintype "passive"))
      (node (ref "C26") (pin "1") (pinfunction "1_1") (pintype "passive"))
      (node (ref "C27") (pin "1") (pinfunction "1_1") (pintype "passive"))
      (node (ref "C28") (pin "1") (pinfunction "1_1") (pintype "passive"))
      (node (ref "C29") (pin "1") (pinfunction "1_1") (pintype "passive"))
      (node (ref "C30") (pin "1") (pinfunction "1_1") (pintype "passive"))
      (node (ref "C31") (pin "1") (pinfunction "1_1") (pintype "passive"))
      (node (ref "C32") (pin "1") (pinfunction "1_1") (pintype "passive"))
      (node (ref "C33") (pin "1") (pinfunction "1_1") (pintype "passive"))
      (node (ref "C34") (pin "1") (pinfunction "1_1") (pintype "passive"))
      (node (ref "C35") (pin "1") (pinfunction "1_1") (pintype "passive"))
      (node (ref "D1") (pin "2") (pinfunction "K_2") (pintype "passive"))
      (node (ref "D10") (pin "2") (pinfunction "K_2") (pintype "passive"))
      (node (ref "D2") (pin "2") (pinfunction "K_2") (pintype "passive"))
      (node (ref "D3") (pin "2") (pinfunction "K_2") (pintype "passive"))
      (node (ref "D4") (pin "2") (pinfunction "K_2") (pintype "passive"))
      (node (ref "D5") (pin "2") (pinfunction "K_2") (pintype "passive"))
      (node (ref "D6") (pin "2") (pinfunction "K_2") (pintype "passive"))
      (node (ref "D7") (pin "2") (pinfunction "K_2") (pintype "passive"))
      (node (ref "D8") (pin "2") (pinfunction "K_2") (pintype "passive"))
      (node (ref "D9") (pin "2") (pinfunction "K_2") (pintype "passive"))
      (node (ref "J1") (pin "1") (pinfunction "P1_1") (pintype "passive"))
      (node (ref "J2") (pin "1") (pinfunction "P1_1") (pintype "passive"))
      (node (ref "MH1") (pin "1") (pinfunction "1_1") (pintype "passive"))
      (node (ref "MH2") (pin "1") (pinfunction "1_1") (pintype "passive"))
      (node (ref "MH3") (pin "1") (pinfunction "1_1") (pintype "passive"))
      (node (ref "MH4") (pin "1") (pinfunction "1_1") (pintype "passive"))
      (node (ref "MH5") (pin "1") (pinfunction "1_1") (pintype "passive"))
      (node (ref "MH6") (pin "1") (pinfunction "1_1") (pintype "passive"))
      (node (ref "P20") (pin "15") (pinfunction "P15_15") (pintype "passive"))
      (node (ref "P20") (pin "19") (pinfunction "P19_19") (pintype "passive"))
      (node (ref "P22") (pin "10") (pinfunction "P10_10") (pintype "passive"))
      (node (ref "P22") (pin "18") (pinfunction "P18_18") (pintype "passive"))
      (node (ref "P22") (pin "4") (pinfunction "P4_4") (pintype "passive"))
      (node (ref "P28") (pin "12") (pinfunction "P12_12") (pintype "passive"))
      (node (ref "P28") (pin "2") (pinfunction "P2_2") (pintype "passive"))
      (node (ref "P9") (pin "1") (pinfunction "P1_1") (pintype "passive"))
      (node (ref "P9") (pin "14") (pinfunction "P14_14") (pintype "passive"))
      (node (ref "P9") (pin "15") (pinfunction "P15_15") (pintype "passive"))
      (node (ref "P9") (pin "16") (pinfunction "P16_16") (pintype "passive"))
      (node (ref "P9") (pin "2") (pinfunction "P2_2") (pintype "passive"))
      (node (ref "P9") (pin "3") (pinfunction "P3_3") (pintype "passive"))
      (node (ref "P9") (pin "8") (pinfunction "P8_8") (pintype "passive"))
      (node (ref "P9") (pin "9") (pinfunction "P9_9") (pintype "passive"))
      (node (ref "PA0") (pin "2") (pinfunction "GND_2") (pintype "passive"))
      (node (ref "PA1") (pin "2") (pinfunction "GND_2") (pintype "passive"))
      (node (ref "PA2") (pin "2") (pinfunction "GND_2") (pintype "passive"))
      (node (ref "PA3") (pin "2") (pinfunction "GND_2") (pintype "passive"))
      (node (ref "PA4") (pin "2") (pinfunction "GND_2") (pintype "passive"))
      (node (ref "PB0") (pin "2") (pinfunction "GND_2") (pintype "passive"))
      (node (ref "PB1") (pin "2") (pinfunction "GND_2") (pintype "passive"))
      (node (ref "PB2") (pin "2") (pinfunction "GND_2") (pintype "passive"))
      (node (ref "PB3") (pin "2") (pinfunction "GND_2") (pintype "passive"))
      (node (ref "PB4") (pin "2") (pinfunction "GND_2") (pintype "passive"))
      (node (ref "R17") (pin "2") (pinfunction "2_2") (pintype "passive"))
      (node (ref "R18") (pin "2") (pinfunction "2_2") (pintype "passive"))
      (node (ref "R19") (pin "2") (pinfunction "2_2") (pintype "passive"))
      (node (ref "R20") (pin "2") (pinfunction "2_2") (pintype "passive"))
      (node (ref "TP14") (pin "1") (pinfunction "1_1") (pintype "passive"))
      (node (ref "U1") (pin "0") (pinfunction "GND_0") (pintype "passive"))
      (node (ref "U1") (pin "1") (pinfunction "GND_1") (pintype "passive"))
      (node (ref "U1") (pin "11") (pinfunction "GND_11") (pintype "passive"))
      (node (ref "U1") (pin "2") (pinfunction "GND_2") (pintype "passive"))
      (node (ref "U1") (pin "5") (pinfunction "GND_5") (pintype "passive"))
      (node (ref "U1") (pin "8") (pinfunction "GND_8") (pintype "passive"))
      (node (ref "U1") (pin "9") (pinfunction "GND_9") (pintype "passive"))
      (node (ref "U10") (pin "2") (pinfunction "GND_2") (pintype "passive"))
      (node (ref "U10") (pin "3") (pinfunction "IN0_3") (pintype "passive"))
      (node (ref "U11") (pin "2") (pinfunction "GND_2") (pintype "passive"))
      (node (ref "U11") (pin "3") (pinfunction "IN0_3") (pintype "passive"))
      (node (ref "U12") (pin "2") (pinfunction "GND_2") (pintype "passive"))
      (node (ref "U12") (pin "3") (pinfunction "IN0_3") (pintype "passive"))
      (node (ref "U13") (pin "2") (pinfunction "GND_2") (pintype "passive"))
      (node (ref "U13") (pin "3") (pinfunction "IN0_3") (pintype "passive"))
      (node (ref "U14") (pin "3") (pinfunction "GND_3") (pintype "passive"))
      (node (ref "U15") (pin "3") (pinfunction "GND_3") (pintype "passive"))
      (node (ref "U16") (pin "2") (pinfunction "GND_2") (pintype "passive"))
      (node (ref "U16") (pin "3") (pinfunction "E_3") (pintype "passive"))
      (node (ref "U2") (pin "0") (pinfunction "GND_0") (pintype "passive"))
      (node (ref "U3") (pin "0") (pinfunction "GND_0") (pintype "passive"))
      (node (ref "U4") (pin "8") (pinfunction "VSS_8") (pintype "passive"))
      (node (ref "U5") (pin "10") (pinfunction "GND_10") (pintype "passive"))
      (node (ref "U6") (pin "2") (pinfunction "GND_2") (pintype "passive"))
      (node (ref "U7") (pin "2") (pinfunction "GND_2") (pintype "passive"))
      (node (ref "U8") (pin "3") (pinfunction "GND_3") (pintype "passive"))
      (node (ref "U9") (pin "3") (pinfunction "GND_3") (pintype "passive"))
    )
    (net (code "31") (name "Net-(D1-A)") (class "Default")
      (node (ref "C1") (pin "1") (pinfunction "1_1") (pintype "passive"))
      (node (ref "D1") (pin "1") (pinfunction "A_1") (pintype "passive"))
      (node (ref "U2") (pin "5") (pinfunction "J1_5") (pintype "passive"))
    )
    (net (code "32") (name "Net-(D2-A)") (class "Default")
      (node (ref "C2") (pin "1") (pinfunction "1_1") (pintype "passive"))
      (node (ref "D2") (pin "1") (pinfunction "A_1") (pintype "passive"))
      (node (ref "U2") (pin "10") (pinfunction "J4_10") (pintype "passive"))
    )
    (net (code "33") (name "Net-(D3-A)") (class "Default")
      (node (ref "C3") (pin "1") (pinfunction "1_1") (pintype "passive"))
      (node (ref "D3") (pin "1") (pinfunction "A_1") (pintype "passive"))
      (node (ref "U3") (pin "1") (pinfunction "J2_1") (pintype "passive"))
    )
    (net (code "34") (name "Net-(D4-A)") (class "Default")
      (node (ref "C4") (pin "1") (pinfunction "1_1") (pintype "passive"))
      (node (ref "D4") (pin "1") (pinfunction "A_1") (pintype "passive"))
      (node (ref "U3") (pin "6") (pinfunction "J3_6") (pintype "passive"))
    )
    (net (code "35") (name "Net-(D5-A)") (class "Default")
      (node (ref "C5") (pin "1") (pinfunction "1_1") (pintype "passive"))
      (node (ref "D5") (pin "1") (pinfunction "A_1") (pintype "passive"))
      (node (ref "U2") (pin "6") (pinfunction "J3_6") (pintype "passive"))
    )
    (net (code "36") (name "Net-(D6-A)") (class "Default")
      (node (ref "C6") (pin "1") (pinfunction "1_1") (pintype "passive"))
      (node (ref "D6") (pin "1") (pinfunction "A_1") (pintype "passive"))
      (node (ref "U2") (pin "1") (pinfunction "J2_1") (pintype "passive"))
    )
    (net (code "37") (name "Net-(D7-A)") (class "Default")
      (node (ref "C7") (pin "1") (pinfunction "1_1") (pintype "passive"))
      (node (ref "D7") (pin "1") (pinfunction "A_1") (pintype "passive"))
      (node (ref "U3") (pin "10") (pinfunction "J4_10") (pintype "passive"))
    )
    (net (code "38") (name "Net-(D8-A)") (class "Default")
      (node (ref "C8") (pin "1") (pinfunction "1_1") (pintype "passive"))
      (node (ref "D8") (pin "1") (pinfunction "A_1") (pintype "passive"))
      (node (ref "U3") (pin "5") (pinfunction "J1_5") (pintype "passive"))
    )
    (net (code "39") (name "Net-(D9-A)") (class "Default")
      (node (ref "C11") (pin "1") (pinfunction "1_1") (pintype "passive"))
      (node (ref "D9") (pin "1") (pinfunction "A_1") (pintype "passive"))
      (node (ref "U1") (pin "10") (pinfunction "RX_10") (pintype "passive"))
    )
    (net (code "40") (name "Net-(D10-A)") (class "Default")
      (node (ref "C12") (pin "1") (pinfunction "1_1") (pintype "passive"))
      (node (ref "D10") (pin "1") (pinfunction "A_1") (pintype "passive"))
      (node (ref "U1") (pin "12") (pinfunction "TX_12") (pintype "passive"))
    )
    (net (code "41") (name "Net-(DA0-K)") (class "Default")
      (node (ref "DA0") (pin "1") (pinfunction "K_1") (pintype "passive"))
      (node (ref "R5") (pin "1") (pinfunction "1_1") (pintype "passive"))
    )
    (net (code "42") (name "Net-(DAG1-K)") (class "Default")
      (node (ref "DAG1") (pin "1") (pinfunction "K_1") (pintype "passive"))
      (node (ref "DAG2") (pin "1") (pinfunction "K_1") (pintype "passive"))
      (node (ref "DAG3") (pin "1") (pinfunction "K_1") (pintype "passive"))
      (node (ref "DAG4") (pin "1") (pinfunction "K_1") (pintype "passive"))
      (node (ref "R1") (pin "1") (pinfunction "1_1") (pintype "passive"))
    )
    (net (code "43") (name "Net-(DAY1-K)") (class "Default")
      (node (ref "DAY1") (pin "1") (pinfunction "K_1") (pintype "passive"))
      (node (ref "DAY2") (pin "1") (pinfunction "K_1") (pintype "passive"))
      (node (ref "DAY3") (pin "1") (pinfunction "K_1") (pintype "passive"))
      (node (ref "DAY4") (pin "1") (pinfunction "K_1") (pintype "passive"))
      (node (ref "R2") (pin "1") (pinfunction "1_1") (pintype "passive"))
    )
    (net (code "44") (name "Net-(DB0-K)") (class "Default")
      (node (ref "DB0") (pin "1") (pinfunction "K_1") (pintype "passive"))
      (node (ref "R6") (pin "1") (pinfunction "1_1") (pintype "passive"))
    )
    (net (code "45") (name "Net-(DBG1-K)") (class "Default")
      (node (ref "DBG1") (pin "1") (pinfunction "K_1") (pintype "passive"))
      (node (ref "DBG2") (pin "1") (pinfunction "K_1") (pintype "passive"))
      (node (ref "DBG3") (pin "1") (pinfunction "K_1") (pintype "passive"))
      (node (ref "DBG4") (pin "1") (pinfunction "K_1") (pintype "passive"))
      (node (ref "R3") (pin "1") (pinfunction "1_1") (pintype "passive"))
    )
    (net (code "46") (name "Net-(DBY1-K)") (class "Default")
      (node (ref "DBY1") (pin "1") (pinfunction "K_1") (pintype "passive"))
      (node (ref "DBY2") (pin "1") (pinfunction "K_1") (pintype "passive"))
      (node (ref "DBY3") (pin "1") (pinfunction "K_1") (pintype "passive"))
      (node (ref "DBY4") (pin "1") (pinfunction "K_1") (pintype "passive"))
      (node (ref "R4") (pin "1") (pinfunction "1_1") (pintype "passive"))
    )
    (net (code "47") (name "Net-(PA0-RF)") (class "Default")
      (node (ref "C11") (pin "2") (pinfunction "2_2") (pintype "passive"))
      (node (ref "PA0") (pin "1") (pinfunction "RF_1") (pintype "passive"))
    )
    (net (code "48") (name "Net-(PA1-RF)") (class "Default")
      (node (ref "C5") (pin "2") (pinfunction "2_2") (pintype "passive"))
      (node (ref "PA1") (pin "1") (pinfunction "RF_1") (pintype "passive"))
    )
    (net (code "49") (name "Net-(PA2-RF)") (class "Default")
      (node (ref "C1") (pin "2") (pinfunction "2_2") (pintype "passive"))
      (node (ref "PA2") (pin "1") (pinfunction "RF_1") (pintype "passive"))
    )
    (net (code "50") (name "Net-(PA3-RF)") (class "Default")
      (node (ref "C6") (pin "2") (pinfunction "2_2") (pintype "passive"))
      (node (ref "PA3") (pin "1") (pinfunction "RF_1") (pintype "passive"))
    )
    (net (code "51") (name "Net-(PA4-RF)") (class "Default")
      (node (ref "C2") (pin "2") (pinfunction "2_2") (pintype "passive"))
      (node (ref "PA4") (pin "1") (pinfunction "RF_1") (pintype "passive"))
    )
    (net (code "52") (name "Net-(PB0-RF)") (class "Default")
      (node (ref "C12") (pin "2") (pinfunction "2_2") (pintype "passive"))
      (node (ref "PB0") (pin "1") (pinfunction "RF_1") (pintype "passive"))
    )
    (net (code "53") (name "Net-(PB1-RF)") (class "Default")
      (node (ref "C7") (pin "2") (pinfunction "2_2") (pintype "passive"))
      (node (ref "PB1") (pin "1") (pinfunction "RF_1") (pintype "passive"))
    )
    (net (code "54") (name "Net-(PB2-RF)") (class "Default")
      (node (ref "C3") (pin "2") (pinfunction "2_2") (pintype "passive"))
      (node (ref "PB2") (pin "1") (pinfunction "RF_1") (pintype "passive"))
    )
    (net (code "55") (name "Net-(PB3-RF)") (class "Default")
      (node (ref "C8") (pin "2") (pinfunction "2_2") (pintype "passive"))
      (node (ref "PB3") (pin "1") (pinfunction "RF_1") (pintype "passive"))
    )
    (net (code "56") (name "Net-(PB4-RF)") (class "Default")
      (node (ref "C4") (pin "2") (pinfunction "2_2") (pintype "passive"))
      (node (ref "PB4") (pin "1") (pinfunction "RF_1") (pintype "passive"))
    )
    (net (code "57") (name "Net-(U1-ANT1)") (class "Default")
      (node (ref "C10") (pin "2") (pinfunction "2_2") (pintype "passive"))
      (node (ref "U1") (pin "4") (pinfunction "ANT1_4") (pintype "passive"))
    )
    (net (code "58") (name "Net-(U1-ANT2)") (class "Default")
      (node (ref "C9") (pin "1") (pinfunction "1_1") (pintype "passive"))
      (node (ref "U1") (pin "6") (pinfunction "ANT2_6") (pintype "passive"))
    )
    (net (code "59") (name "Net-(U2-RFC)") (class "Default")
      (node (ref "C9") (pin "2") (pinfunction "2_2") (pintype "passive"))
      (node (ref "U2") (pin "8") (pinfunction "RFC_8") (pintype "passive"))
    )
    (net (code "60") (name "Net-(U3-RFC)") (class "Default")
      (node (ref "C10") (pin "1") (pinfunction "1_1") (pintype "passive"))
      (node (ref "U3") (pin "8") (pinfunction "RFC_8") (pintype "passive"))
    )
    (net (code "61") (name "Net-(U6-Y)") (class "Default")
      (node (ref "R1") (pin "2") (pinfunction "2_2") (pintype "passive"))
      (node (ref "R4") (pin "2") (pinfunction "2_2") (pintype "passive"))
      (node (ref "U6") (pin "4") (pinfunction "Y_4") (pintype "passive"))
    )
    (net (code "62") (name "Net-(U7-Y)") (class "Default")
      (node (ref "R2") (pin "2") (pinfunction "2_2") (pintype "passive"))
      (node (ref "R3") (pin "2") (pinfunction "2_2") (pintype "passive"))
      (node (ref "U7") (pin "4") (pinfunction "Y_4") (pintype "passive"))
    )
    (net (code "63") (name "VCC") (class "Default")
      (node (ref "C23") (pin "2") (pinfunction "2_2") (pintype "passive"))
      (node (ref "C24") (pin "2") (pinfunction "2_2") (pintype "passive"))
      (node (ref "C25") (pin "2") (pinfunction "2_2") (pintype "passive"))
      (node (ref "C26") (pin "2") (pinfunction "2_2") (pintype "passive"))
      (node (ref "C27") (pin "2") (pinfunction "2_2") (pintype "passive"))
      (node (ref "C28") (pin "2") (pinfunction "2_2") (pintype "passive"))
      (node (ref "C29") (pin "2") (pinfunction "2_2") (pintype "passive"))
      (node (ref "C30") (pin "2") (pinfunction "2_2") (pintype "passive"))
      (node (ref "C31") (pin "2") (pinfunction "2_2") (pintype "passive"))
      (node (ref "C32") (pin "2") (pinfunction "2_2") (pintype "passive"))
      (node (ref "C33") (pin "2") (pinfunction "2_2") (pintype "passive"))
      (node (ref "C34") (pin "2") (pinfunction "2_2") (pintype "passive"))
      (node (ref "C35") (pin "2") (pinfunction "2_2") (pintype "passive"))
      (node (ref "DA0") (pin "2") (pinfunction "A_2") (pintype "passive"))
      (node (ref "DB0") (pin "2") (pinfunction "A_2") (pintype "passive"))
      (node (ref "J1") (pin "2") (pinfunction "P2_2") (pintype "passive"))
      (node (ref "P1") (pin "1") (pinfunction "P1_1") (pintype "passive"))
      (node (ref "P1") (pin "3") (pinfunction "P3_3") (pintype "passive"))
      (node (ref "P1") (pin "5") (pinfunction "P5_5") (pintype "passive"))
      (node (ref "P20") (pin "3") (pinfunction "P3_3") (pintype "passive"))
      (node (ref "P22") (pin "11") (pinfunction "P11_11") (pintype "passive"))
      (node (ref "P28") (pin "1") (pinfunction "P1_1") (pintype "passive"))
      (node (ref "R10") (pin "2") (pinfunction "2_2") (pintype "passive"))
      (node (ref "R11") (pin "2") (pinfunction "2_2") (pintype "passive"))
      (node (ref "R12") (pin "2") (pinfunction "2_2") (pintype "passive"))
      (node (ref "R13") (pin "2") (pinfunction "2_2") (pintype "passive"))
      (node (ref "R14") (pin "2") (pinfunction "2_2") (pintype "passive"))
      (node (ref "R15") (pin "2") (pinfunction "2_2") (pintype "passive"))
      (node (ref "R16") (pin "2") (pinfunction "2_2") (pintype "passive"))
      (node (ref "R7") (pin "1") (pinfunction "1_1") (pintype "passive"))
      (node (ref "R8") (pin "1") (pinfunction "1_1") (pintype "passive"))
      (node (ref "R9") (pin "1") (pinfunction "1_1") (pintype "passive"))
      (node (ref "TP15") (pin "1") (pinfunction "1_1") (pintype "passive"))
      (node (ref "U10") (pin "5") (pinfunction "VCC_5") (pintype "passive"))
      (node (ref "U11") (pin "5") (pinfunction "VCC_5") (pintype "passive"))
      (node (ref "U12") (pin "5") (pinfunction "VCC_5") (pintype "passive"))
      (node (ref "U13") (pin "5") (pinfunction "VCC_5") (pintype "passive"))
      (node (ref "U14") (pin "5") (pinfunction "VCC_5") (pintype "passive"))
      (node (ref "U15") (pin "5") (pinfunction "VCC_5") (pintype "passive"))
      (node (ref "U16") (pin "5") (pinfunction "VCC_5") (pintype "passive"))
      (node (ref "U4") (pin "16") (pinfunction "VDD_16") (pintype "passive"))
      (node (ref "U5") (pin "20") (pinfunction "VCC_20") (pintype "passive"))
      (node (ref "U6") (pin "3") (pinfunction "IN0_3") (pintype "passive"))
      (node (ref "U6") (pin "5") (pinfunction "VCC_5") (pintype "passive"))
      (node (ref "U7") (pin "3") (pinfunction "IN0_3") (pintype "passive"))
      (node (ref "U7") (pin "5") (pinfunction "VCC_5") (pintype "passive"))
      (node (ref "U8") (pin "5") (pinfunction "VCC_5") (pintype "passive"))
      (node (ref "U9") (pin "5") (pinfunction "VCC_5") (pintype "passive"))
    )
    (net (code "64") (name "unconnected-(J1-P3-Pad3)") (class "Default")
      (node (ref "J1") (pin "3") (pinfunction "P3_3") (pintype "passive+no_connect"))
    )
    (net (code "65") (name "unconnected-(J1-P4-Pad4)") (class "Default")
      (node (ref "J1") (pin "4") (pinfunction "P4_4") (pintype "passive+no_connect"))
    )
    (net (code "66") (name "unconnected-(J1-P5-Pad5)") (class "Default")
      (node (ref "J1") (pin "5") (pinfunction "P5_5") (pintype "passive+no_connect"))
    )
    (net (code "67") (name "unconnected-(J1-P6-Pad6)") (class "Default")
      (node (ref "J1") (pin "6") (pinfunction "P6_6") (pintype "passive+no_connect"))
    )
    (net (code "68") (name "unconnected-(J1-P7-Pad7)") (class "Default")
      (node (ref "J1") (pin "7") (pinfunction "P7_7") (pintype "passive+no_connect"))
    )
    (net (code "69") (name "unconnected-(J1-P8-Pad8)") (class "Default")
      (node (ref "J1") (pin "8") (pinfunction "P8_8") (pintype "passive+no_connect"))
    )
    (net (code "70") (name "unconnected-(J1-P9-Pad9)") (class "Default")
      (node (ref "J1") (pin "9") (pinfunction "P9_9") (pintype "passive+no_connect"))
    )
    (net (code "71") (name "unconnected-(J1-P10-Pad10)") (class "Default")
      (node (ref "J1") (pin "10") (pinfunction "P10_10") (pintype "passive+no_connect"))
    )
    (net (code "72") (name "unconnected-(J1-P11-Pad11)") (class "Default")
      (node (ref "J1") (pin "11") (pinfunction "P11_11") (pintype "passive+no_connect"))
    )
    (net (code "73") (name "unconnected-(J1-P12-Pad12)") (class "Default")
      (node (ref "J1") (pin "12") (pinfunction "P12_12") (pintype "passive+no_connect"))
    )
    (net (code "74") (name "unconnected-(J1-P13-Pad13)") (class "Default")
      (node (ref "J1") (pin "13") (pinfunction "P13_13") (pintype "passive+no_connect"))
    )
    (net (code "75") (name "unconnected-(J1-P14-Pad14)") (class "Default")
      (node (ref "J1") (pin "14") (pinfunction "P14_14") (pintype "passive+no_connect"))
    )
    (net (code "76") (name "unconnected-(J1-P15-Pad15)") (class "Default")
      (node (ref "J1") (pin "15") (pinfunction "P15_15") (pintype "passive+no_connect"))
    )
    (net (code "77") (name "unconnected-(J1-P16-Pad16)") (class "Default")
      (node (ref "J1") (pin "16") (pinfunction "P16_16") (pintype "passive+no_connect"))
    )
    (net (code "78") (name "unconnected-(J1-P17-Pad17)") (class "Default")
      (node (ref "J1") (pin "17") (pinfunction "P17_17") (pintype "passive+no_connect"))
    )
    (net (code "79") (name "unconnected-(J1-P18-Pad18)") (class "Default")
      (node (ref "J1") (pin "18") (pinfunction "P18_18") (pintype "passive+no_connect"))
    )
    (net (code "80") (name "unconnected-(J1-P19-Pad19)") (class "Default")
      (node (ref "J1") (pin "19") (pinfunction "P19_19") (pintype "passive+no_connect"))
    )
    (net (code "81") (name "unconnected-(J1-P20-Pad20)") (class "Default")
      (node (ref "J1") (pin "20") (pinfunction "P20_20") (pintype "passive+no_connect"))
    )
    (net (code "82") (name "unconnected-(J1-P21-Pad21)") (class "Default")
      (node (ref "J1") (pin "21") (pinfunction "P21_21") (pintype "passive+no_connect"))
    )
    (net (code "83") (name "unconnected-(J1-P22-Pad22)") (class "Default")
      (node (ref "J1") (pin "22") (pinfunction "P22_22") (pintype "passive+no_connect"))
    )
    (net (code "84") (name "unconnected-(J1-P23-Pad23)") (class "Default")
      (node (ref "J1") (pin "23") (pinfunction "P23_23") (pintype "passive+no_connect"))
    )
    (net (code "85") (name "unconnected-(J1-P24-Pad24)") (class "Default")
      (node (ref "J1") (pin "24") (pinfunction "P24_24") (pintype "passive+no_connect"))
    )
    (net (code "86") (name "unconnected-(J1-P25-Pad25)") (class "Default")
      (node (ref "J1") (pin "25") (pinfunction "P25_25") (pintype "passive+no_connect"))
    )
    (net (code "87") (name "unconnected-(J1-P26-Pad26)") (class "Default")
      (node (ref "J1") (pin "26") (pinfunction "P26_26") (pintype "passive+no_connect"))
    )
    (net (code "88") (name "unconnected-(J1-P27-Pad27)") (class "Default")
      (node (ref "J1") (pin "27") (pinfunction "P27_27") (pintype "passive+no_connect"))
    )
    (net (code "89") (name "unconnected-(J1-P28-Pad28)") (class "Default")
      (node (ref "J1") (pin "28") (pinfunction "P28_28") (pintype "passive+no_connect"))
    )
    (net (code "90") (name "unconnected-(J1-P29-Pad29)") (class "Default")
      (node (ref "J1") (pin "29") (pinfunction "P29_29") (pintype "passive+no_connect"))
    )
    (net (code "91") (name "unconnected-(J1-P30-Pad30)") (class "Default")
      (node (ref "J1") (pin "30") (pinfunction "P30_30") (pintype "passive+no_connect"))
    )
    (net (code "92") (name "unconnected-(J1-P31-Pad31)") (class "Default")
      (node (ref "J1") (pin "31") (pinfunction "P31_31") (pintype "passive+no_connect"))
    )
    (net (code "93") (name "unconnected-(J1-P32-Pad32)") (class "Default")
      (node (ref "J1") (pin "32") (pinfunction "P32_32") (pintype "passive+no_connect"))
    )
    (net (code "94") (name "unconnected-(J1-P33-Pad33)") (class "Default")
      (node (ref "J1") (pin "33") (pinfunction "P33_33") (pintype "passive+no_connect"))
    )
    (net (code "95") (name "unconnected-(J1-P34-Pad34)") (class "Default")
      (node (ref "J1") (pin "34") (pinfunction "P34_34") (pintype "passive+no_connect"))
    )
    (net (code "96") (name "unconnected-(J1-P35-Pad35)") (class "Default")
      (node (ref "J1") (pin "35") (pinfunction "P35_35") (pintype "passive+no_connect"))
    )
    (net (code "97") (name "unconnected-(J1-P36-Pad36)") (class "Default")
      (node (ref "J1") (pin "36") (pinfunction "P36_36") (pintype "passive+no_connect"))
    )
    (net (code "98") (name "unconnected-(J1-P37-Pad37)") (class "Default")
      (node (ref "J1") (pin "37") (pinfunction "P37_37") (pintype "passive+no_connect"))
    )
    (net (code "99") (name "unconnected-(J1-P38-Pad38)") (class "Default")
      (node (ref "J1") (pin "38") (pinfunction "P38_38") (pintype "passive+no_connect"))
    )
    (net (code "100") (name "unconnected-(J1-P39-Pad39)") (class "Default")
      (node (ref "J1") (pin "39") (pinfunction "P39_39") (pintype "passive+no_connect"))
    )
    (net (code "101") (name "unconnected-(J1-P40-Pad40)") (class "Default")
      (node (ref "J1") (pin "40") (pinfunction "P40_40") (pintype "passive+no_connect"))
    )
    (net (code "102") (name "unconnected-(J2-P2-Pad2)") (class "Default")
      (node (ref "J2") (pin "2") (pinfunction "P2_2") (pintype "passive+no_connect"))
    )
    (net (code "103") (name "unconnected-(J2-P3-Pad3)") (class "Default")
      (node (ref "J2") (pin "3") (pinfunction "P3_3") (pintype "passive+no_connect"))
    )
    (net (code "104") (name "unconnected-(J2-P4-Pad4)") (class "Default")
      (node (ref "J2") (pin "4") (pinfunction "P4_4") (pintype "passive+no_connect"))
    )
    (net (code "105") (name "unconnected-(J2-P5-Pad5)") (class "Default")
      (node (ref "J2") (pin "5") (pinfunction "P5_5") (pintype "passive+no_connect"))
    )
    (net (code "106") (name "unconnected-(J2-P11-Pad11)") (class "Default")
      (node (ref "J2") (pin "11") (pinfunction "P11_11") (pintype "passive+no_connect"))
    )
    (net (code "107") (name "unconnected-(J2-P12-Pad12)") (class "Default")
      (node (ref "J2") (pin "12") (pinfunction "P12_12") (pintype "passive+no_connect"))
    )
    (net (code "108") (name "unconnected-(J2-P13-Pad13)") (class "Default")
      (node (ref "J2") (pin "13") (pinfunction "P13_13") (pintype "passive+no_connect"))
    )
    (net (code "109") (name "unconnected-(J2-P14-Pad14)") (class "Default")
      (node (ref "J2") (pin "14") (pinfunction "P14_14") (pintype "passive+no_connect"))
    )
    (net (code "110") (name "unconnected-(J2-P15-Pad15)") (class "Default")
      (node (ref "J2") (pin "15") (pinfunction "P15_15") (pintype "passive+no_connect"))
    )
    (net (code "111") (name "unconnected-(J2-P16-Pad16)") (class "Default")
      (node (ref "J2") (pin "16") (pinfunction "P16_16") (pintype "passive+no_connect"))
    )
    (net (code "112") (name "unconnected-(J2-P17-Pad17)") (class "Default")
      (node (ref "J2") (pin "17") (pinfunction "P17_17") (pintype "passive+no_connect"))
    )
    (net (code "113") (name "unconnected-(J2-P18-Pad18)") (class "Default")
      (node (ref "J2") (pin "18") (pinfunction "P18_18") (pintype "passive+no_connect"))
    )
    (net (code "114") (name "unconnected-(J2-P19-Pad19)") (class "Default")
      (node (ref "J2") (pin "19") (pinfunction "P19_19") (pintype "passive+no_connect"))
    )
    (net (code "115") (name "unconnected-(J2-P20-Pad20)") (class "Default")
      (node (ref "J2") (pin "20") (pinfunction "P20_20") (pintype "passive+no_connect"))
    )
    (net (code "116") (name "unconnected-(J2-P21-Pad21)") (class "Default")
      (node (ref "J2") (pin "21") (pinfunction "P21_21") (pintype "passive+no_connect"))
    )
    (net (code "117") (name "unconnected-(J2-P22-Pad22)") (class "Default")
      (node (ref "J2") (pin "22") (pinfunction "P22_22") (pintype "passive+no_connect"))
    )
    (net (code "118") (name "unconnected-(J2-P23-Pad23)") (class "Default")
      (node (ref "J2") (pin "23") (pinfunction "P23_23") (pintype "passive+no_connect"))
    )
    (net (code "119") (name "unconnected-(J2-P24-Pad24)") (class "Default")
      (node (ref "J2") (pin "24") (pinfunction "P24_24") (pintype "passive+no_connect"))
    )
    (net (code "120") (name "unconnected-(J2-P25-Pad25)") (class "Default")
      (node (ref "J2") (pin "25") (pinfunction "P25_25") (pintype "passive+no_connect"))
    )
    (net (code "121") (name "unconnected-(J2-P26-Pad26)") (class "Default")
      (node (ref "J2") (pin "26") (pinfunction "P26_26") (pintype "passive+no_connect"))
    )
    (net (code "122") (name "unconnected-(J2-P27-Pad27)") (class "Default")
      (node (ref "J2") (pin "27") (pinfunction "P27_27") (pintype "passive+no_connect"))
    )
    (net (code "123") (name "unconnected-(J2-P28-Pad28)") (class "Default")
      (node (ref "J2") (pin "28") (pinfunction "P28_28") (pintype "passive+no_connect"))
    )
    (net (code "124") (name "unconnected-(J2-P29-Pad29)") (class "Default")
      (node (ref "J2") (pin "29") (pinfunction "P29_29") (pintype "passive+no_connect"))
    )
    (net (code "125") (name "unconnected-(J2-P30-Pad30)") (class "Default")
      (node (ref "J2") (pin "30") (pinfunction "P30_30") (pintype "passive+no_connect"))
    )
    (net (code "126") (name "unconnected-(J2-P31-Pad31)") (class "Default")
      (node (ref "J2") (pin "31") (pinfunction "P31_31") (pintype "passive+no_connect"))
    )
    (net (code "127") (name "unconnected-(J2-P32-Pad32)") (class "Default")
      (node (ref "J2") (pin "32") (pinfunction "P32_32") (pintype "passive+no_connect"))
    )
    (net (code "128") (name "unconnected-(J2-P33-Pad33)") (class "Default")
      (node (ref "J2") (pin "33") (pinfunction "P33_33") (pintype "passive+no_connect"))
    )
    (net (code "129") (name "unconnected-(J2-P34-Pad34)") (class "Default")
      (node (ref "J2") (pin "34") (pinfunction "P34_34") (pintype "passive+no_connect"))
    )
    (net (code "130") (name "unconnected-(J2-P35-Pad35)") (class "Default")
      (node (ref "J2") (pin "35") (pinfunction "P35_35") (pintype "passive+no_connect"))
    )
    (net (code "131") (name "unconnected-(J2-P36-Pad36)") (class "Default")
      (node (ref "J2") (pin "36") (pinfunction "P36_36") (pintype "passive+no_connect"))
    )
    (net (code "132") (name "unconnected-(J2-P37-Pad37)") (class "Default")
      (node (ref "J2") (pin "37") (pinfunction "P37_37") (pintype "passive+no_connect"))
    )
    (net (code "133") (name "unconnected-(J2-P38-Pad38)") (class "Default")
      (node (ref "J2") (pin "38") (pinfunction "P38_38") (pintype "passive+no_connect"))
    )
    (net (code "134") (name "unconnected-(P9-P4-Pad4)") (class "Default")
      (node (ref "P9") (pin "4") (pinfunction "P4_4") (pintype "passive+no_connect"))
    )
    (net (code "135") (name "unconnected-(P9-P5-Pad5)") (class "Default")
      (node (ref "P9") (pin "5") (pinfunction "P5_5") (pintype "passive+no_connect"))
    )
    (net (code "136") (name "unconnected-(P9-P6-Pad6)") (class "Default")
      (node (ref "P9") (pin "6") (pinfunction "P6_6") (pintype "passive+no_connect"))
    )
    (net (code "137") (name "unconnected-(P9-P7-Pad7)") (class "Default")
      (node (ref "P9") (pin "7") (pinfunction "P7_7") (pintype "passive+no_connect"))
    )
    (net (code "138") (name "unconnected-(P9-P10-Pad10)") (class "Default")
      (node (ref "P9") (pin "10") (pinfunction "P10_10") (pintype "passive+no_connect"))
    )
    (net (code "139") (name "unconnected-(P9-P11-Pad11)") (class "Default")
      (node (ref "P9") (pin "11") (pinfunction "P11_11") (pintype "passive+no_connect"))
    )
    (net (code "140") (name "unconnected-(P9-P12-Pad12)") (class "Default")
      (node (ref "P9") (pin "12") (pinfunction "P12_12") (pintype "passive+no_connect"))
    )
    (net (code "141") (name "unconnected-(P9-P13-Pad13)") (class "Default")
      (node (ref "P9") (pin "13") (pinfunction "P13_13") (pintype "passive+no_connect"))
    )
    (net (code "142") (name "unconnected-(P20-P1-Pad1)") (class "Default")
      (node (ref "P20") (pin "1") (pinfunction "P1_1") (pintype "passive+no_connect"))
    )
    (net (code "143") (name "unconnected-(P20-P2-Pad2)") (class "Default")
      (node (ref "P20") (pin "2") (pinfunction "P2_2") (pintype "passive+no_connect"))
    )
    (net (code "144") (name "unconnected-(P20-P4-Pad4)") (class "Default")
      (node (ref "P20") (pin "4") (pinfunction "P4_4") (pintype "passive+no_connect"))
    )
    (net (code "145") (name "unconnected-(P20-P6-Pad6)") (class "Default")
      (node (ref "P20") (pin "6") (pinfunction "P6_6") (pintype "passive+no_connect"))
    )
    (net (code "146") (name "unconnected-(P20-P7-Pad7)") (class "Default")
      (node (ref "P20") (pin "7") (pinfunction "P7_7") (pintype "passive+no_connect"))
    )
    (net (code "147") (name "unconnected-(P20-P8-Pad8)") (class "Default")
      (node (ref "P20") (pin "8") (pinfunction "P8_8") (pintype "passive+no_connect"))
    )
    (net (code "148") (name "unconnected-(P20-P13-Pad13)") (class "Default")
      (node (ref "P20") (pin "13") (pinfunction "P13_13") (pintype "passive+no_connect"))
    )
    (net (code "149") (name "unconnected-(P20-P14-Pad14)") (class "Default")
      (node (ref "P20") (pin "14") (pinfunction "P14_14") (pintype "passive+no_connect"))
    )
    (net (code "150") (name "unconnected-(P20-P16-Pad16)") (class "Default")
      (node (ref "P20") (pin "16") (pinfunction "P16_16") (pintype "passive+no_connect"))
    )
    (net (code "151") (name "unconnected-(P20-P17-Pad17)") (class "Default")
      (node (ref "P20") (pin "17") (pinfunction "P17_17") (pintype "passive+no_connect"))
    )
    (net (code "152") (name "unconnected-(P20-P18-Pad18)") (class "Default")
      (node (ref "P20") (pin "18") (pinfunction "P18_18") (pintype "passive+no_connect"))
    )
    (net (code "153") (name "unconnected-(P20-P20-Pad20)") (class "Default")
      (node (ref "P20") (pin "20") (pinfunction "P20_20") (pintype "passive+no_connect"))
    )
    (net (code "154") (name "unconnected-(P20-P21-Pad21)") (class "Default")
      (node (ref "P20") (pin "21") (pinfunction "P21_21") (pintype "passive+no_connect"))
    )
    (net (code "155") (name "unconnected-(P20-P22-Pad22)") (class "Default")
      (node (ref "P20") (pin "22") (pinfunction "P22_22") (pintype "passive+no_connect"))
    )
    (net (code "156") (name "unconnected-(P22-P1-Pad1)") (class "Default")
      (node (ref "P22") (pin "1") (pinfunction "P1_1") (pintype "passive+no_connect"))
    )
    (net (code "157") (name "unconnected-(P22-P2-Pad2)") (class "Default")
      (node (ref "P22") (pin "2") (pinfunction "P2_2") (pintype "passive+no_connect"))
    )
    (net (code "158") (name "unconnected-(P22-P3-Pad3)") (class "Default")
      (node (ref "P22") (pin "3") (pinfunction "P3_3") (pintype "passive+no_connect"))
    )
    (net (code "159") (name "unconnected-(P22-P5-Pad5)") (class "Default")
      (node (ref "P22") (pin "5") (pinfunction "P5_5") (pintype "passive+no_connect"))
    )
    (net (code "160") (name "unconnected-(P22-P6-Pad6)") (class "Default")
      (node (ref "P22") (pin "6") (pinfunction "P6_6") (pintype "passive+no_connect"))
    )
    (net (code "161") (name "unconnected-(P22-P7-Pad7)") (class "Default")
      (node (ref "P22") (pin "7") (pinfunction "P7_7") (pintype "passive+no_connect"))
    )
    (net (code "162") (name "unconnected-(P22-P8-Pad8)") (class "Default")
      (node (ref "P22") (pin "8") (pinfunction "P8_8") (pintype "passive+no_connect"))
    )
    (net (code "163") (name "unconnected-(P22-P9-Pad9)") (class "Default")
      (node (ref "P22") (pin "9") (pinfunction "P9_9") (pintype "passive+no_connect"))
    )
    (net (code "164") (name "unconnected-(P22-P12-Pad12)") (class "Default")
      (node (ref "P22") (pin "12") (pinfunction "P12_12") (pintype "passive+no_connect"))
    )
    (net (code "165") (name "unconnected-(P22-P13-Pad13)") (class "Default")
      (node (ref "P22") (pin "13") (pinfunction "P13_13") (pintype "passive+no_connect"))
    )
    (net (code "166") (name "unconnected-(P22-P14-Pad14)") (class "Default")
      (node (ref "P22") (pin "14") (pinfunction "P14_14") (pintype "passive+no_connect"))
    )
    (net (code "167") (name "unconnected-(P22-P15-Pad15)") (class "Default")
      (node (ref "P22") (pin "15") (pinfunction "P15_15") (pintype "passive+no_connect"))
    )
    (net (code "168") (name "unconnected-(P22-P16-Pad16)") (class "Default")
      (node (ref "P22") (pin "16") (pinfunction "P16_16") (pintype "passive+no_connect"))
    )
    (net (code "169") (name "unconnected-(P22-P17-Pad17)") (class "Default")
      (node (ref "P22") (pin "17") (pinfunction "P17_17") (pintype "passive+no_connect"))
    )
    (net (code "170") (name "unconnected-(P22-P19-Pad19)") (class "Default")
      (node (ref "P22") (pin "19") (pinfunction "P19_19") (pintype "passive+no_connect"))
    )
    (net (code "171") (name "unconnected-(P22-P20-Pad20)") (class "Default")
      (node (ref "P22") (pin "20") (pinfunction "P20_20") (pintype "passive+no_connect"))
    )
    (net (code "172") (name "unconnected-(P22-P21-Pad21)") (class "Default")
      (node (ref "P22") (pin "21") (pinfunction "P21_21") (pintype "passive+no_connect"))
    )
    (net (code "173") (name "unconnected-(P22-P22-Pad22)") (class "Default")
      (node (ref "P22") (pin "22") (pinfunction "P22_22") (pintype "passive+no_connect"))
    )
    (net (code "174") (name "unconnected-(P22-P23-Pad23)") (class "Default")
      (node (ref "P22") (pin "23") (pinfunction "P23_23") (pintype "passive+no_connect"))
    )
    (net (code "175") (name "unconnected-(P22-P25-Pad25)") (class "Default")
      (node (ref "P22") (pin "25") (pinfunction "P25_25") (pintype "passive+no_connect"))
    )
    (net (code "176") (name "unconnected-(P28-P3-Pad3)") (class "Default")
      (node (ref "P28") (pin "3") (pinfunction "P3_3") (pintype "passive+no_connect"))
    )
    (net (code "177") (name "unconnected-(P28-P4-Pad4)") (class "Default")
      (node (ref "P28") (pin "4") (pinfunction "P4_4") (pintype "passive+no_connect"))
    )
    (net (code "178") (name "unconnected-(P28-P5-Pad5)") (class "Default")
      (node (ref "P28") (pin "5") (pinfunction "P5_5") (pintype "passive+no_connect"))
    )
    (net (code "179") (name "unconnected-(P28-P6-Pad6)") (class "Default")
      (node (ref "P28") (pin "6") (pinfunction "P6_6") (pintype "passive+no_connect"))
    )
    (net (code "180") (name "unconnected-(P28-P7-Pad7)") (class "Default")
      (node (ref "P28") (pin "7") (pinfunction "P7_7") (pintype "passive+no_connect"))
    )
    (net (code "181") (name "unconnected-(P28-P8-Pad8)") (class "Default")
      (node (ref "P28") (pin "8") (pinfunction "P8_8") (pintype "passive+no_connect"))
    )
    (net (code "182") (name "unconnected-(P28-P9-Pad9)") (class "Default")
      (node (ref "P28") (pin "9") (pinfunction "P9_9") (pintype "passive+no_connect"))
    )
    (net (code "183") (name "unconnected-(P28-P10-Pad10)") (class "Default")
      (node (ref "P28") (pin "10") (pinfunction "P10_10") (pintype "passive+no_connect"))
    )
    (net (code "184") (name "unconnected-(P28-P11-Pad11)") (class "Default")
      (node (ref "P28") (pin "11") (pinfunction "P11_11") (pintype "passive+no_connect"))
    )
    (net (code "185") (name "unconnected-(P28-P13-Pad13)") (class "Default")
      (node (ref "P28") (pin "13") (pinfunction "P13_13") (pintype "passive+no_connect"))
    )
    (net (code "186") (name "unconnected-(P28-P14-Pad14)") (class "Default")
      (node (ref "P28") (pin "14") (pinfunction "P14_14") (pintype "passive+no_connect"))
    )
    (net (code "187") (name "unconnected-(P28-P15-Pad15)") (class "Default")
      (node (ref "P28") (pin "15") (pinfunction "P15_15") (pintype "passive+no_connect"))
    )
    (net (code "188") (name "unconnected-(P28-P16-Pad16)") (class "Default")
      (node (ref "P28") (pin "16") (pinfunction "P16_16") (pintype "passive+no_connect"))
    )
    (net (code "189") (name "unconnected-(P28-P17-Pad17)") (class "Default")
      (node (ref "P28") (pin "17") (pinfunction "P17_17") (pintype "passive+no_connect"))
    )
    (net (code "190") (name "unconnected-(P28-P18-Pad18)") (class "Default")
      (node (ref "P28") (pin "18") (pinfunction "P18_18") (pintype "passive+no_connect"))
    )
    (net (code "191") (name "unconnected-(P28-P19-Pad19)") (class "Default")
      (node (ref "P28") (pin "19") (pinfunction "P19_19") (pintype "passive+no_connect"))
    )
    (net (code "192") (name "unconnected-(P28-P20-Pad20)") (class "Default")
      (node (ref "P28") (pin "20") (pinfunction "P20_20") (pintype "passive+no_connect"))
    )
    (net (code "193") (name "unconnected-(P28-P21-Pad21)") (class "Default")
      (node (ref "P28") (pin "21") (pinfunction "P21_21") (pintype "passive+no_connect"))
    )
    (net (code "194") (name "unconnected-(P28-P22-Pad22)") (class "Default")
      (node (ref "P28") (pin "22") (pinfunction "P22_22") (pintype "passive+no_connect"))
    )
    (net (code "195") (name "unconnected-(U2-NC-Pad3)") (class "Default")
      (node (ref "U2") (pin "3") (pinfunction "NC_3") (pintype "passive"))
    )
    (net (code "196") (name "unconnected-(U3-NC-Pad3)") (class "Default")
      (node (ref "U3") (pin "3") (pinfunction "NC_3") (pintype "passive"))
    )
    (net (code "197") (name "unconnected-(U5-A6-Pad7)") (class "Default")
      (node (ref "U5") (pin "7") (pinfunction "A6_7") (pintype "passive+no_connect"))
    )
    (net (code "198") (name "unconnected-(U5-A7-Pad8)") (class "Default")
      (node (ref "U5") (pin "8") (pinfunction "A7_8") (pintype "passive+no_connect"))
    )
    (net (code "199") (name "unconnected-(U5-A8-Pad9)") (class "Default")
      (node (ref "U5") (pin "9") (pinfunction "A8_9") (pintype "passive+no_connect"))
    )
    (net (code "200") (name "unconnected-(U5-B6-Pad13)") (class "Default")
      (node (ref "U5") (pin "13") (pinfunction "B6_13") (pintype "passive+no_connect"))
    )
    (net (code "201") (name "unconnected-(U5-B7-Pad12)") (class "Default")
      (node (ref "U5") (pin "12") (pinfunction "B7_12") (pintype "passive+no_connect"))
    )
    (net (code "202") (name "unconnected-(U5-B8-Pad11)") (class "Default")
      (node (ref "U5") (pin "11") (pinfunction "B8_11") (pintype "passive+no_connect"))
    )
    (net (code "203") (name "unconnected-(U5-NC-Pad1)") (class "Default")
      (node (ref "U5") (pin "1") (pinfunction "NC_1") (pintype "passive"))
    )
  )
)
